# AMR3350.net
KiCad netlist of a schematic drawn in EAGLE
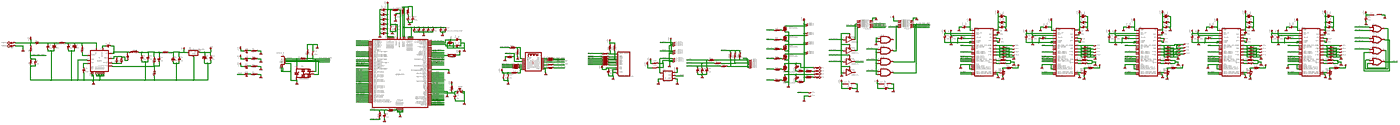
[diagram p0: schematic, sheet 1, overview]
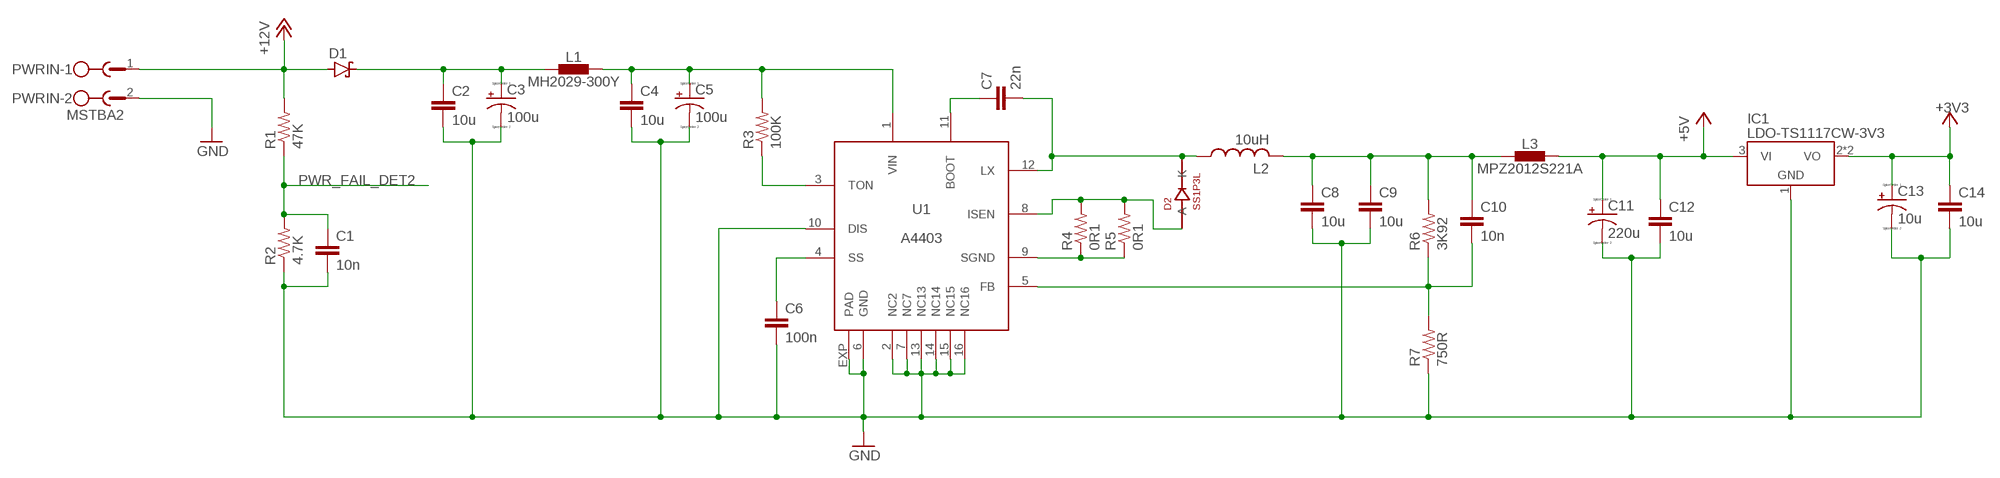
[diagram p1: schematic, sheet 1, part 1 of 8]
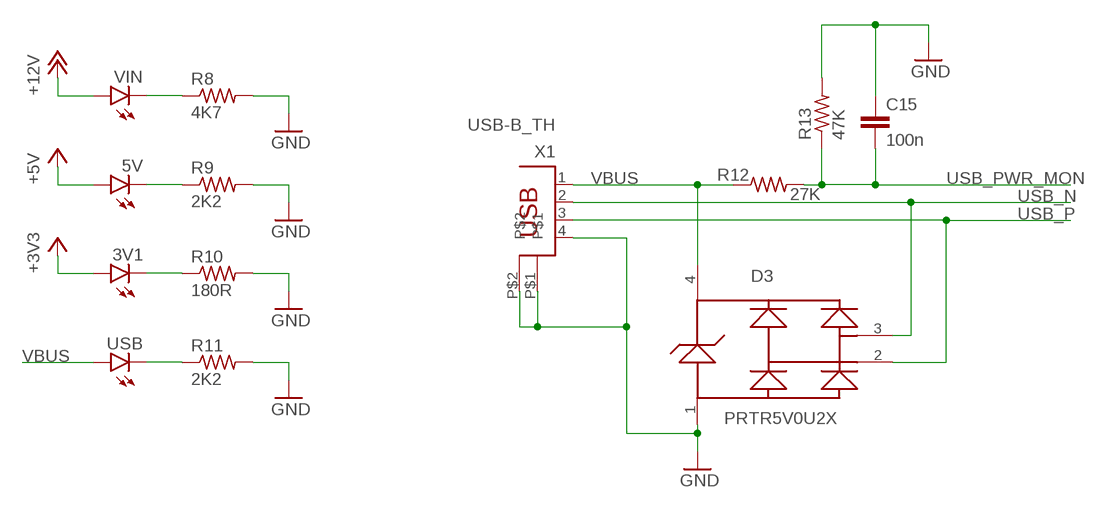
[diagram p2: schematic, sheet 1, part 2 of 8]
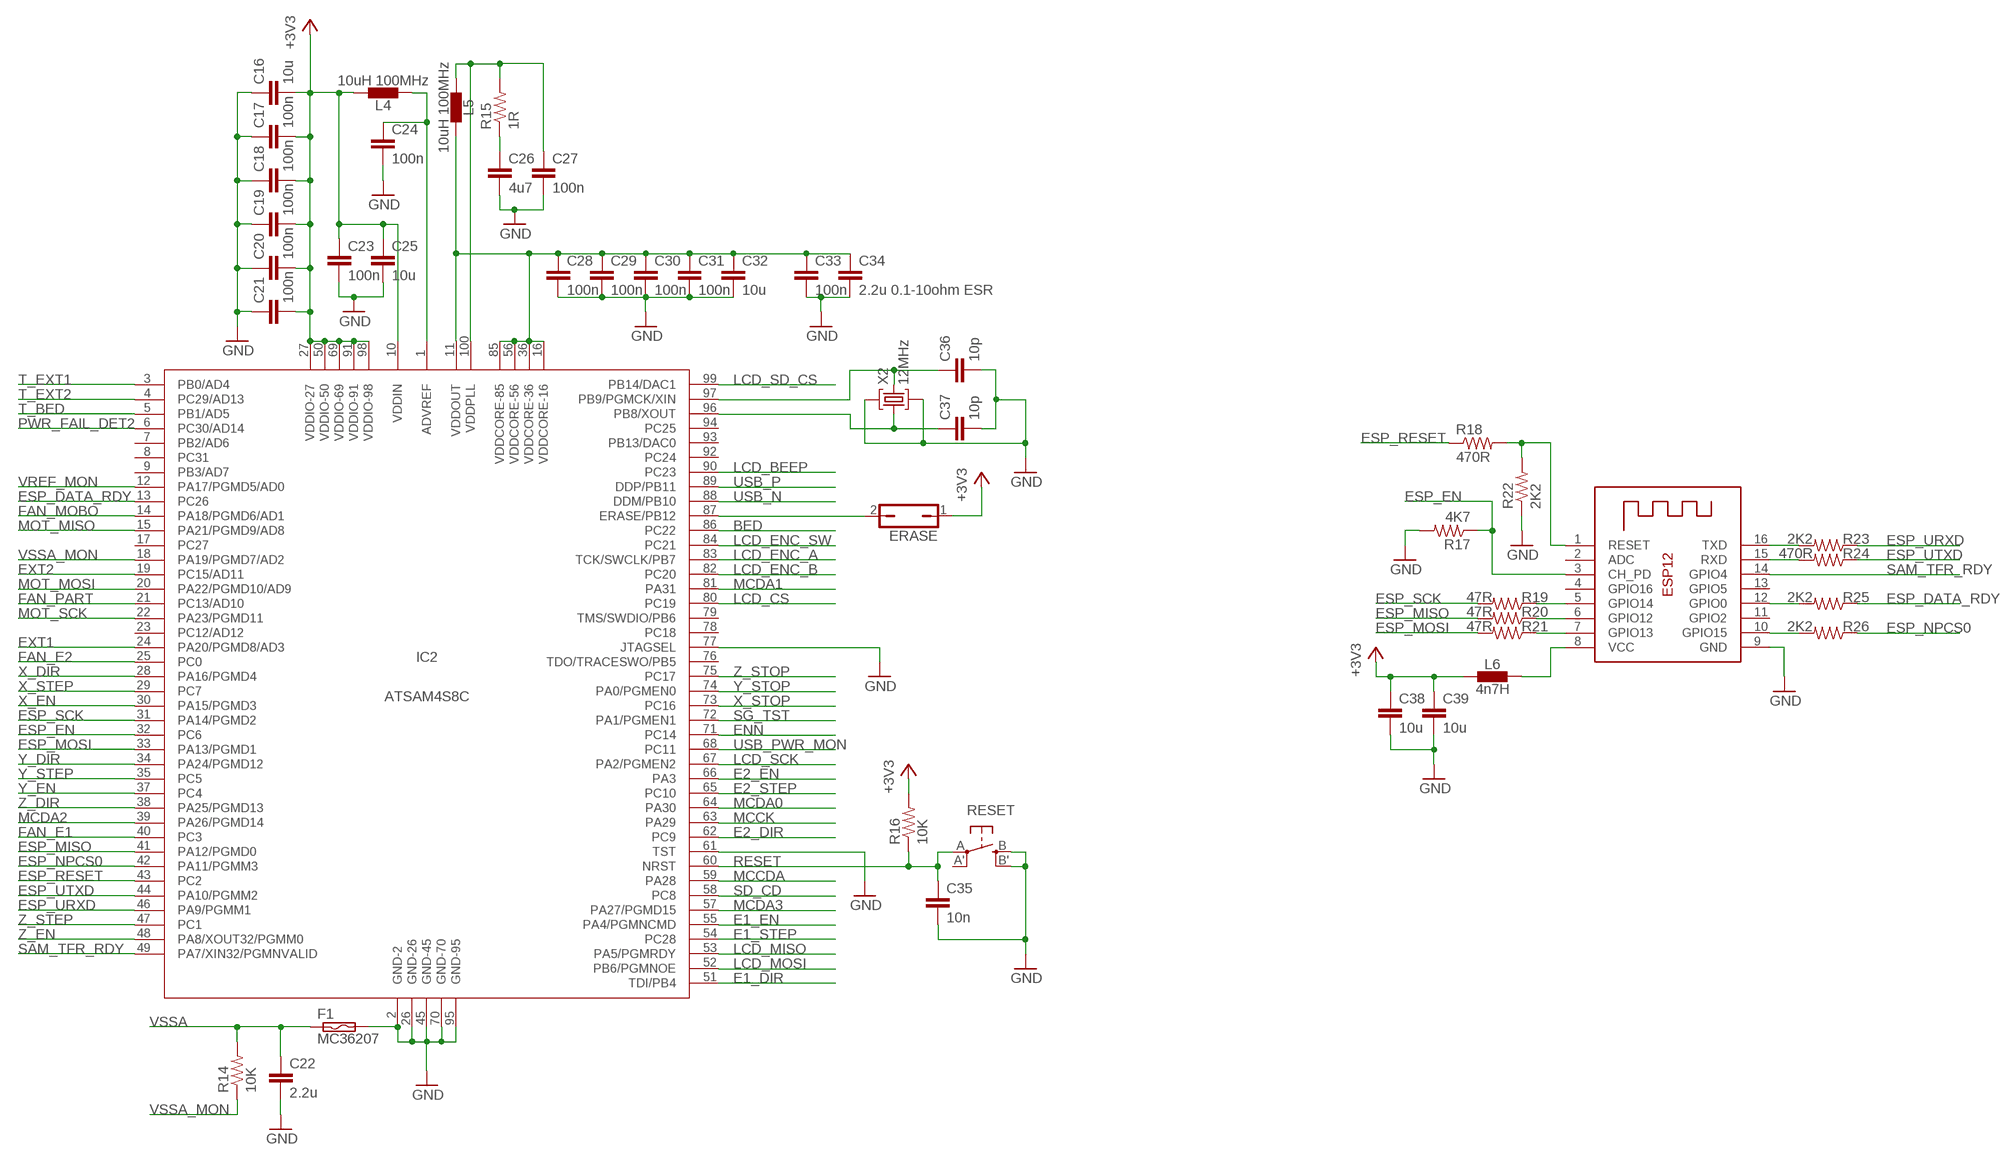
[diagram p3: schematic, sheet 1, part 3 of 8]
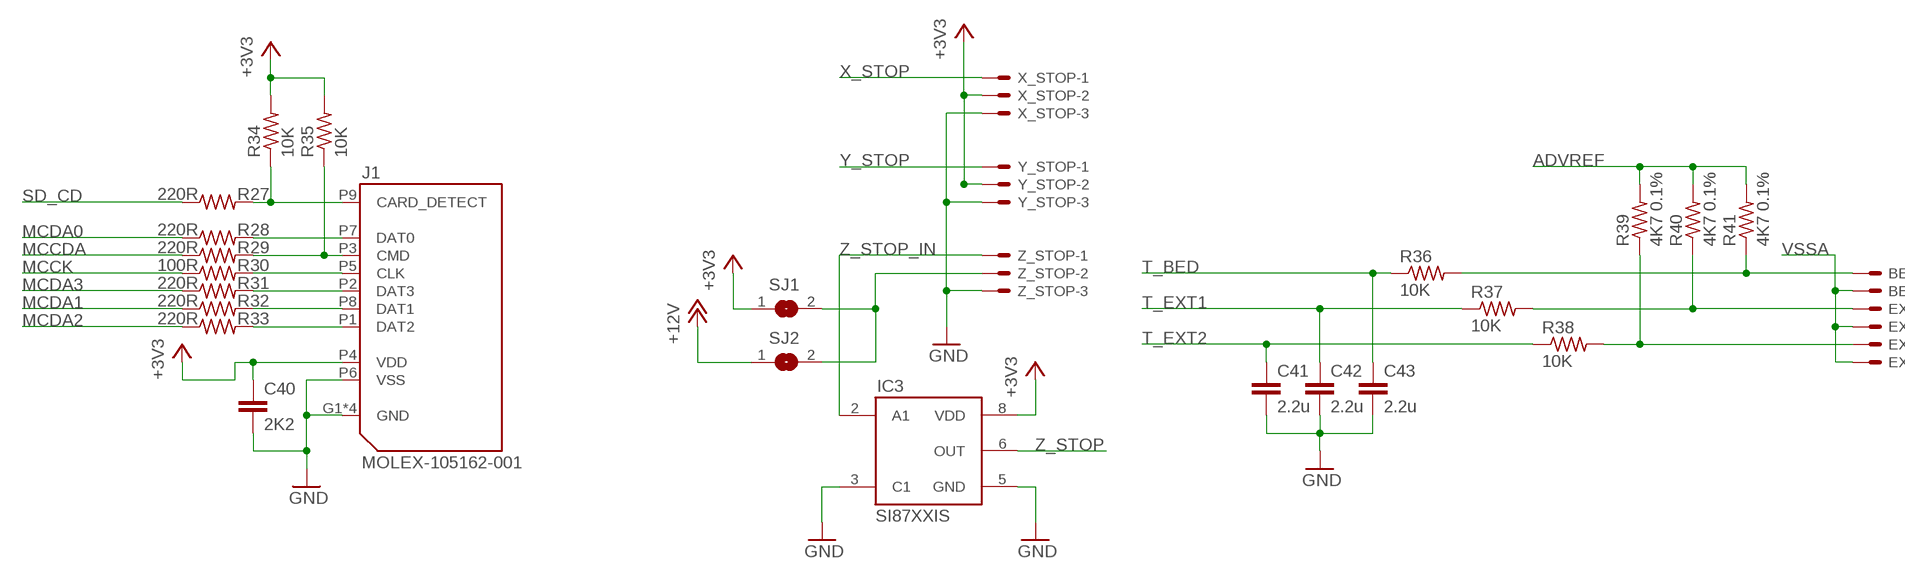
[diagram p4: schematic, sheet 1, part 4 of 8]
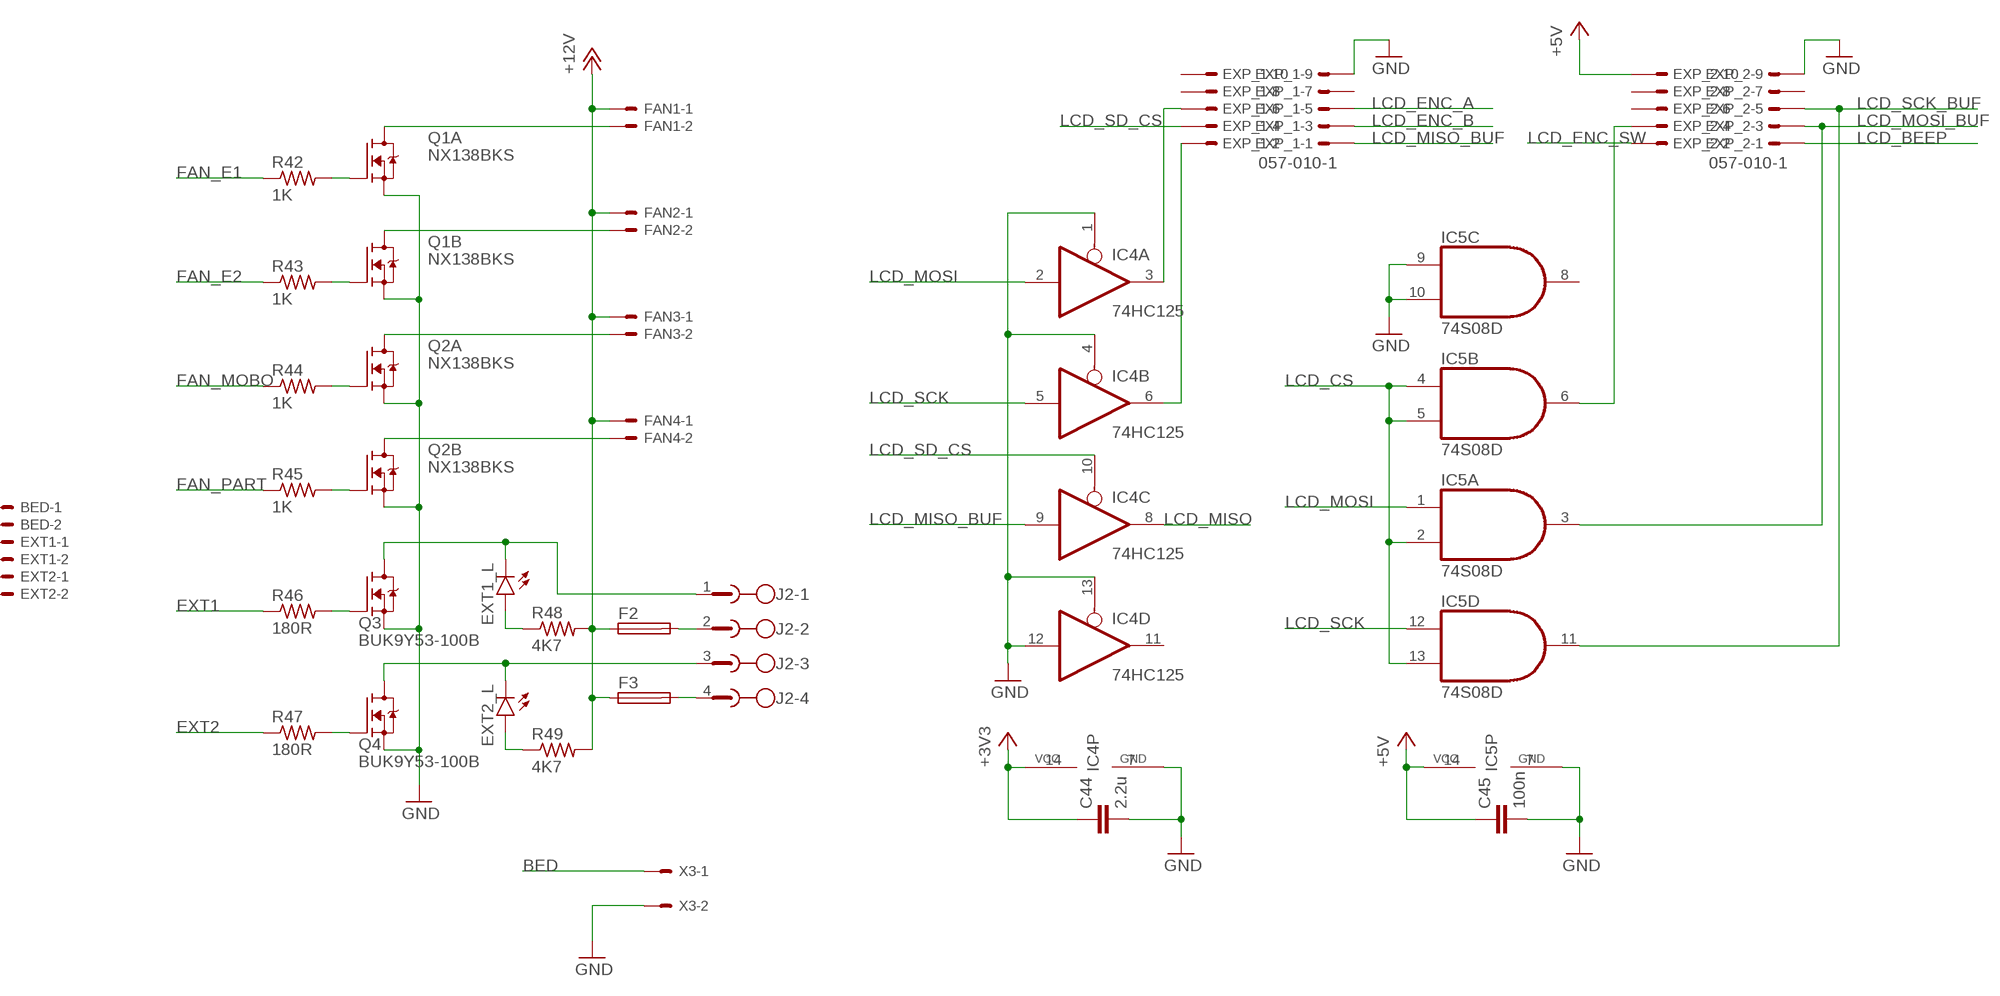
[diagram p5: schematic, sheet 1, part 5 of 8]
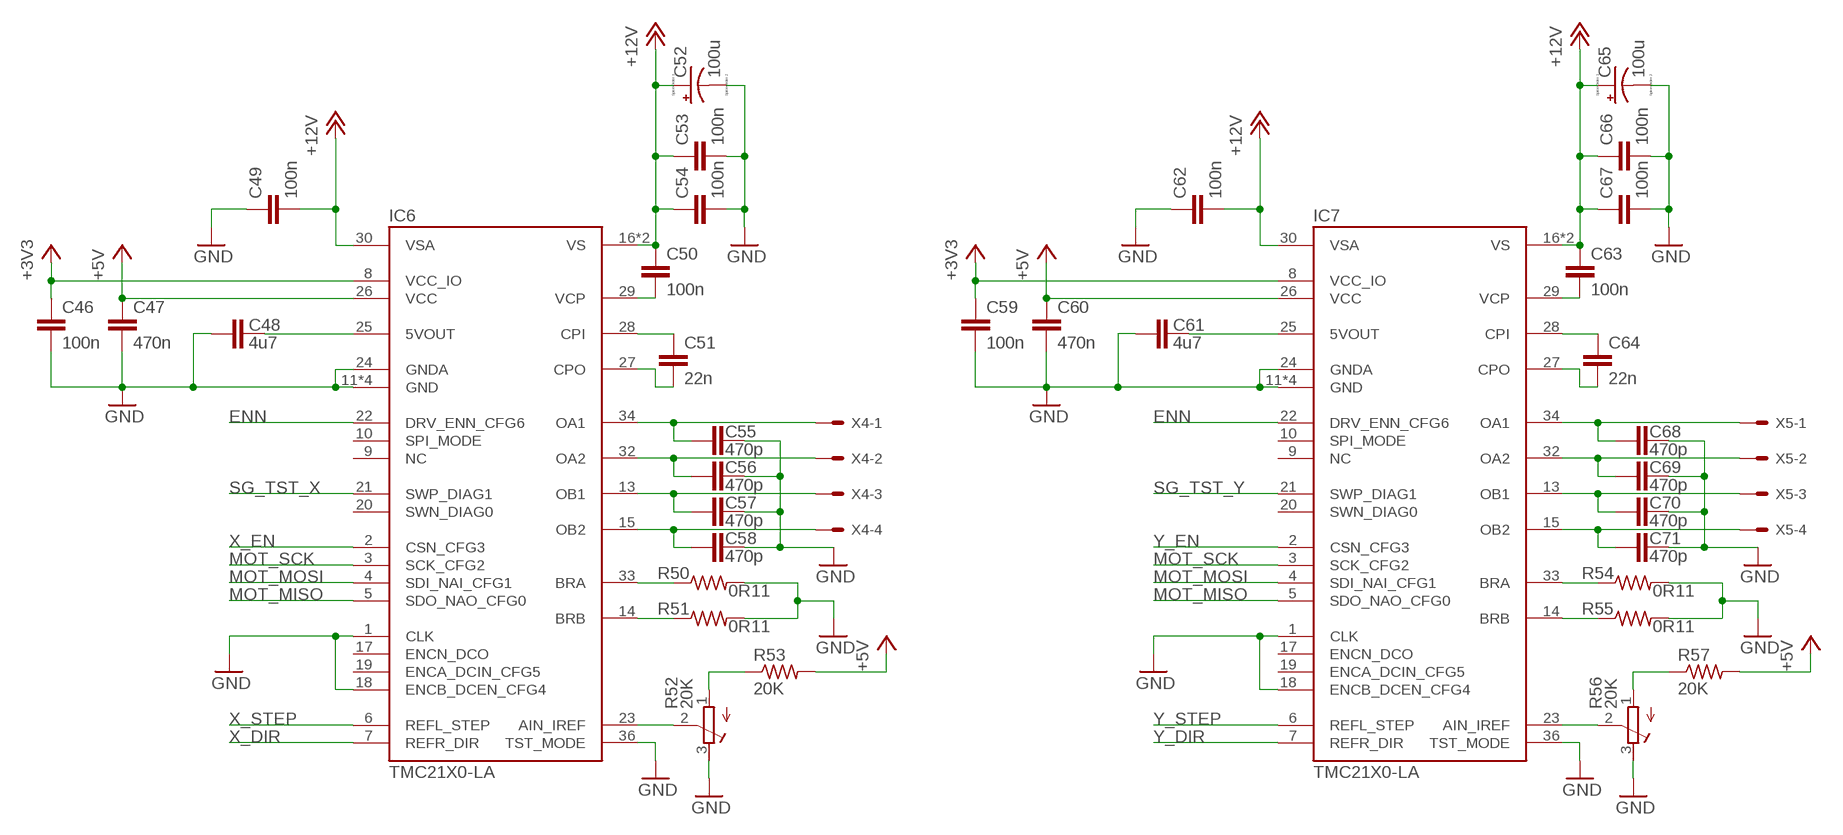
[diagram p6: schematic, sheet 1, part 6 of 8]
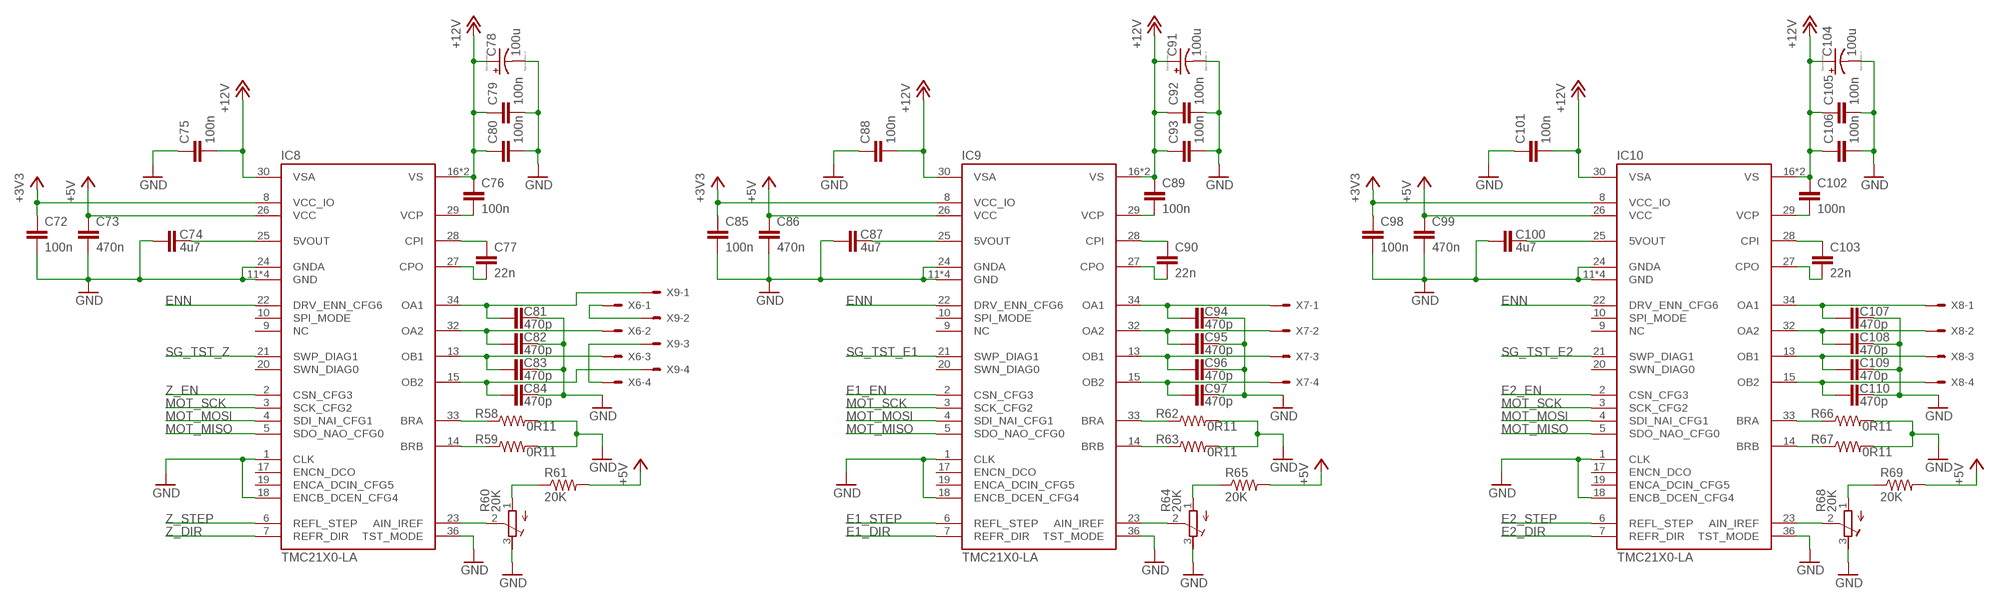
[diagram p7: schematic, sheet 1, part 7 of 8]
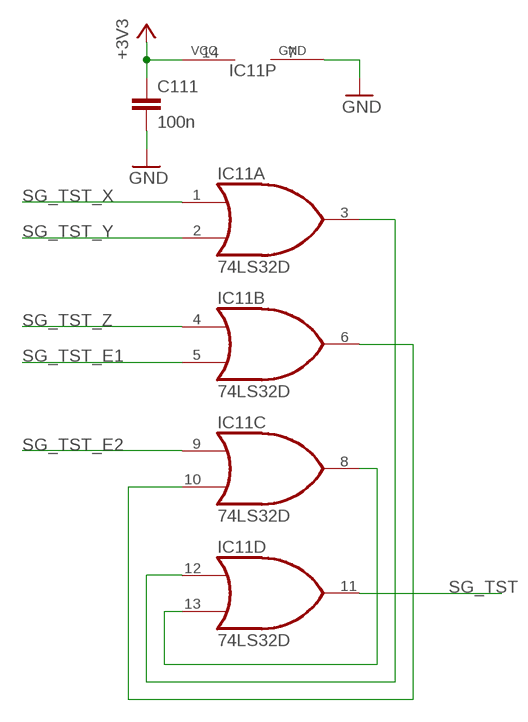
[diagram p8: schematic, sheet 1, part 8 of 8]

(export (version "E")
  (design (tool "Eeschema 10.0.6"))
  (components
    (comp (ref "3V1")
      (value "LEDCHIPLED_0805")
      (footprint "eagle-import:CHIPLED_0805")
      (libsource (lib "eagle-import") (part "LEDCHIPLED_0805"))
    )
    (comp (ref "5V")
      (value "LEDCHIPLED_0805")
      (footprint "eagle-import:CHIPLED_0805")
      (libsource (lib "eagle-import") (part "LEDCHIPLED_0805"))
    )
    (comp (ref "BED")
      (value "KK-254-2")
      (footprint "eagle-import:MOLEX-KK-254-2")
      (libsource (lib "eagle-import") (part "KK-254-2"))
    )
    (comp (ref "C1")
      (value "10n")
      (footprint "eagle-import:C0603")
      (libsource (lib "eagle-import") (part "resistor_348_C-EUC0603"))
    )
    (comp (ref "C2")
      (value "10u")
      (footprint "eagle-import:C0603")
      (libsource (lib "eagle-import") (part "resistor_348_C-EUC0603"))
    )
    (comp (ref "C3")
      (value "100u")
      (footprint "eagle-import:PANASONIC_D")
      (libsource (lib "eagle-import") (part "CPOL-USD"))
    )
    (comp (ref "C4")
      (value "10u")
      (footprint "eagle-import:C0603")
      (libsource (lib "eagle-import") (part "resistor_348_C-EUC0603"))
    )
    (comp (ref "C5")
      (value "100u")
      (footprint "eagle-import:PANASONIC_D")
      (libsource (lib "eagle-import") (part "CPOL-USD"))
    )
    (comp (ref "C6")
      (value "100n")
      (footprint "eagle-import:C0603")
      (libsource (lib "eagle-import") (part "resistor_348_C-EUC0603"))
    )
    (comp (ref "C7")
      (value "22n")
      (footprint "eagle-import:C0603")
      (libsource (lib "eagle-import") (part "resistor_348_C-EUC0603"))
    )
    (comp (ref "C8")
      (value "10u")
      (footprint "eagle-import:C0603")
      (libsource (lib "eagle-import") (part "resistor_348_C-EUC0603"))
    )
    (comp (ref "C9")
      (value "10u")
      (footprint "eagle-import:C0603")
      (libsource (lib "eagle-import") (part "resistor_348_C-EUC0603"))
    )
    (comp (ref "C10")
      (value "10n")
      (footprint "eagle-import:C0603")
      (libsource (lib "eagle-import") (part "resistor_348_C-EUC0603"))
    )
    (comp (ref "C11")
      (value "220u")
      (footprint "eagle-import:PANASONIC_D")
      (libsource (lib "eagle-import") (part "CPOL-USD"))
    )
    (comp (ref "C12")
      (value "10u")
      (footprint "eagle-import:C0603")
      (libsource (lib "eagle-import") (part "resistor_348_C-EUC0603"))
    )
    (comp (ref "C13")
      (value "10u")
      (footprint "eagle-import:PANASONIC_D")
      (libsource (lib "eagle-import") (part "CPOL-USD"))
    )
    (comp (ref "C14")
      (value "10u")
      (footprint "eagle-import:C0603")
      (libsource (lib "eagle-import") (part "resistor_348_C-EUC0603"))
    )
    (comp (ref "C15")
      (value "100n")
      (footprint "eagle-import:C0603")
      (libsource (lib "eagle-import") (part "resistor_348_C-EUC0603"))
    )
    (comp (ref "C16")
      (value "10u")
      (footprint "eagle-import:C0805")
      (libsource (lib "eagle-import") (part "resistor_348_C-EUC0805"))
    )
    (comp (ref "C17")
      (value "100n")
      (footprint "eagle-import:C0603")
      (libsource (lib "eagle-import") (part "resistor_348_C-EUC0603"))
    )
    (comp (ref "C18")
      (value "100n")
      (footprint "eagle-import:C0603")
      (libsource (lib "eagle-import") (part "resistor_348_C-EUC0603"))
    )
    (comp (ref "C19")
      (value "100n")
      (footprint "eagle-import:C0603")
      (libsource (lib "eagle-import") (part "resistor_348_C-EUC0603"))
    )
    (comp (ref "C20")
      (value "100n")
      (footprint "eagle-import:C0603")
      (libsource (lib "eagle-import") (part "resistor_348_C-EUC0603"))
    )
    (comp (ref "C21")
      (value "100n")
      (footprint "eagle-import:C0603")
      (libsource (lib "eagle-import") (part "resistor_348_C-EUC0603"))
    )
    (comp (ref "C22")
      (value "2.2u")
      (footprint "eagle-import:C0603")
      (libsource (lib "eagle-import") (part "resistor_348_C-EUC0603"))
    )
    (comp (ref "C23")
      (value "100n")
      (footprint "eagle-import:C0603")
      (libsource (lib "eagle-import") (part "resistor_348_C-EUC0603"))
    )
    (comp (ref "C24")
      (value "100n")
      (footprint "eagle-import:C0603")
      (libsource (lib "eagle-import") (part "resistor_348_C-EUC0603"))
    )
    (comp (ref "C25")
      (value "10u")
      (footprint "eagle-import:C0603")
      (libsource (lib "eagle-import") (part "resistor_348_C-EUC0603"))
    )
    (comp (ref "C26")
      (value "4u7")
      (footprint "eagle-import:C0603")
      (libsource (lib "eagle-import") (part "resistor_348_C-EUC0603"))
    )
    (comp (ref "C27")
      (value "100n")
      (footprint "eagle-import:C0603")
      (libsource (lib "eagle-import") (part "resistor_348_C-EUC0603"))
    )
    (comp (ref "C28")
      (value "100n")
      (footprint "eagle-import:C0603")
      (libsource (lib "eagle-import") (part "resistor_348_C-EUC0603"))
    )
    (comp (ref "C29")
      (value "100n")
      (footprint "eagle-import:C0603")
      (libsource (lib "eagle-import") (part "resistor_348_C-EUC0603"))
    )
    (comp (ref "C30")
      (value "100n")
      (footprint "eagle-import:C0603")
      (libsource (lib "eagle-import") (part "resistor_348_C-EUC0603"))
    )
    (comp (ref "C31")
      (value "100n")
      (footprint "eagle-import:C0603")
      (libsource (lib "eagle-import") (part "resistor_348_C-EUC0603"))
    )
    (comp (ref "C32")
      (value "10u")
      (footprint "eagle-import:C0805")
      (libsource (lib "eagle-import") (part "resistor_348_C-EUC0805"))
    )
    (comp (ref "C33")
      (value "100n")
      (footprint "eagle-import:C0603")
      (libsource (lib "eagle-import") (part "resistor_348_C-EUC0603"))
    )
    (comp (ref "C34")
      (value "2.2u 0.1-10ohm ESR")
      (footprint "eagle-import:C0603")
      (libsource (lib "eagle-import") (part "resistor_348_C-EUC0603"))
    )
    (comp (ref "C35")
      (value "10n")
      (footprint "eagle-import:C0603")
      (libsource (lib "eagle-import") (part "resistor_348_C-EUC0603"))
    )
    (comp (ref "C36")
      (value "10p")
      (footprint "eagle-import:C0603")
      (libsource (lib "eagle-import") (part "resistor_348_C-EUC0603"))
    )
    (comp (ref "C37")
      (value "10p")
      (footprint "eagle-import:C0603")
      (libsource (lib "eagle-import") (part "resistor_348_C-EUC0603"))
    )
    (comp (ref "C38")
      (value "10u")
      (footprint "eagle-import:C0603")
      (libsource (lib "eagle-import") (part "resistor_348_C-EUC0603"))
    )
    (comp (ref "C39")
      (value "10u")
      (footprint "eagle-import:C0603")
      (libsource (lib "eagle-import") (part "resistor_348_C-EUC0603"))
    )
    (comp (ref "C40")
      (value "2K2")
      (footprint "eagle-import:C0603")
      (libsource (lib "eagle-import") (part "resistor_348_C-EUC0603"))
    )
    (comp (ref "C41")
      (value "2.2u")
      (footprint "eagle-import:C0603")
      (libsource (lib "eagle-import") (part "resistor_348_C-EUC0603"))
    )
    (comp (ref "C42")
      (value "2.2u")
      (footprint "eagle-import:C0603")
      (libsource (lib "eagle-import") (part "resistor_348_C-EUC0603"))
    )
    (comp (ref "C43")
      (value "2.2u")
      (footprint "eagle-import:C0603")
      (libsource (lib "eagle-import") (part "resistor_348_C-EUC0603"))
    )
    (comp (ref "C44")
      (value "2.2u")
      (footprint "eagle-import:C0603")
      (libsource (lib "eagle-import") (part "resistor_348_C-EUC0603"))
    )
    (comp (ref "C45")
      (value "100n")
      (footprint "eagle-import:C0603")
      (libsource (lib "eagle-import") (part "resistor_348_C-EUC0603"))
    )
    (comp (ref "C46")
      (value "100n")
      (footprint "eagle-import:C0603")
      (libsource (lib "eagle-import") (part "resistor_348_C-EUC0603"))
    )
    (comp (ref "C47")
      (value "470n")
      (footprint "eagle-import:C0603")
      (libsource (lib "eagle-import") (part "resistor_348_C-EUC0603"))
    )
    (comp (ref "C48")
      (value "4u7")
      (footprint "eagle-import:C0603")
      (libsource (lib "eagle-import") (part "resistor_348_C-EUC0603"))
    )
    (comp (ref "C49")
      (value "100n")
      (footprint "eagle-import:C0603")
      (libsource (lib "eagle-import") (part "resistor_348_C-EUC0603"))
    )
    (comp (ref "C50")
      (value "100n")
      (footprint "eagle-import:C0603")
      (libsource (lib "eagle-import") (part "resistor_348_C-EUC0603"))
    )
    (comp (ref "C51")
      (value "22n")
      (footprint "eagle-import:C0603")
      (libsource (lib "eagle-import") (part "resistor_348_C-EUC0603"))
    )
    (comp (ref "C52")
      (value "100u")
      (footprint "eagle-import:PANASONIC_D")
      (libsource (lib "eagle-import") (part "CPOL-USD"))
    )
    (comp (ref "C53")
      (value "100n")
      (footprint "eagle-import:C0603")
      (libsource (lib "eagle-import") (part "resistor_348_C-EUC0603"))
    )
    (comp (ref "C54")
      (value "100n")
      (footprint "eagle-import:C0603")
      (libsource (lib "eagle-import") (part "resistor_348_C-EUC0603"))
    )
    (comp (ref "C55")
      (value "470p")
      (footprint "eagle-import:C0402")
      (libsource (lib "eagle-import") (part "resistor_348_C-EUC0402"))
    )
    (comp (ref "C56")
      (value "470p")
      (footprint "eagle-import:C0402")
      (libsource (lib "eagle-import") (part "resistor_348_C-EUC0402"))
    )
    (comp (ref "C57")
      (value "470p")
      (footprint "eagle-import:C0402")
      (libsource (lib "eagle-import") (part "resistor_348_C-EUC0402"))
    )
    (comp (ref "C58")
      (value "470p")
      (footprint "eagle-import:C0402")
      (libsource (lib "eagle-import") (part "resistor_348_C-EUC0402"))
    )
    (comp (ref "C59")
      (value "100n")
      (footprint "eagle-import:C0603")
      (libsource (lib "eagle-import") (part "resistor_348_C-EUC0603"))
    )
    (comp (ref "C60")
      (value "470n")
      (footprint "eagle-import:C0603")
      (libsource (lib "eagle-import") (part "resistor_348_C-EUC0603"))
    )
    (comp (ref "C61")
      (value "4u7")
      (footprint "eagle-import:C0603")
      (libsource (lib "eagle-import") (part "resistor_348_C-EUC0603"))
    )
    (comp (ref "C62")
      (value "100n")
      (footprint "eagle-import:C0603")
      (libsource (lib "eagle-import") (part "resistor_348_C-EUC0603"))
    )
    (comp (ref "C63")
      (value "100n")
      (footprint "eagle-import:C0603")
      (libsource (lib "eagle-import") (part "resistor_348_C-EUC0603"))
    )
    (comp (ref "C64")
      (value "22n")
      (footprint "eagle-import:C0603")
      (libsource (lib "eagle-import") (part "resistor_348_C-EUC0603"))
    )
    (comp (ref "C65")
      (value "100u")
      (footprint "eagle-import:PANASONIC_D")
      (libsource (lib "eagle-import") (part "CPOL-USD"))
    )
    (comp (ref "C66")
      (value "100n")
      (footprint "eagle-import:C0603")
      (libsource (lib "eagle-import") (part "resistor_348_C-EUC0603"))
    )
    (comp (ref "C67")
      (value "100n")
      (footprint "eagle-import:C0603")
      (libsource (lib "eagle-import") (part "resistor_348_C-EUC0603"))
    )
    (comp (ref "C68")
      (value "470p")
      (footprint "eagle-import:C0402")
      (libsource (lib "eagle-import") (part "resistor_348_C-EUC0402"))
    )
    (comp (ref "C69")
      (value "470p")
      (footprint "eagle-import:C0402")
      (libsource (lib "eagle-import") (part "resistor_348_C-EUC0402"))
    )
    (comp (ref "C70")
      (value "470p")
      (footprint "eagle-import:C0402")
      (libsource (lib "eagle-import") (part "resistor_348_C-EUC0402"))
    )
    (comp (ref "C71")
      (value "470p")
      (footprint "eagle-import:C0402")
      (libsource (lib "eagle-import") (part "resistor_348_C-EUC0402"))
    )
    (comp (ref "C72")
      (value "100n")
      (footprint "eagle-import:C0603")
      (libsource (lib "eagle-import") (part "resistor_348_C-EUC0603"))
    )
    (comp (ref "C73")
      (value "470n")
      (footprint "eagle-import:C0603")
      (libsource (lib "eagle-import") (part "resistor_348_C-EUC0603"))
    )
    (comp (ref "C74")
      (value "4u7")
      (footprint "eagle-import:C0603")
      (libsource (lib "eagle-import") (part "resistor_348_C-EUC0603"))
    )
    (comp (ref "C75")
      (value "100n")
      (footprint "eagle-import:C0603")
      (libsource (lib "eagle-import") (part "resistor_348_C-EUC0603"))
    )
    (comp (ref "C76")
      (value "100n")
      (footprint "eagle-import:C0603")
      (libsource (lib "eagle-import") (part "resistor_348_C-EUC0603"))
    )
    (comp (ref "C77")
      (value "22n")
      (footprint "eagle-import:C0603")
      (libsource (lib "eagle-import") (part "resistor_348_C-EUC0603"))
    )
    (comp (ref "C78")
      (value "100u")
      (footprint "eagle-import:PANASONIC_D")
      (libsource (lib "eagle-import") (part "CPOL-USD"))
    )
    (comp (ref "C79")
      (value "100n")
      (footprint "eagle-import:C0603")
      (libsource (lib "eagle-import") (part "resistor_348_C-EUC0603"))
    )
    (comp (ref "C80")
      (value "100n")
      (footprint "eagle-import:C0603")
      (libsource (lib "eagle-import") (part "resistor_348_C-EUC0603"))
    )
    (comp (ref "C81")
      (value "470p")
      (footprint "eagle-import:C0402")
      (libsource (lib "eagle-import") (part "resistor_348_C-EUC0402"))
    )
    (comp (ref "C82")
      (value "470p")
      (footprint "eagle-import:C0402")
      (libsource (lib "eagle-import") (part "resistor_348_C-EUC0402"))
    )
    (comp (ref "C83")
      (value "470p")
      (footprint "eagle-import:C0402")
      (libsource (lib "eagle-import") (part "resistor_348_C-EUC0402"))
    )
    (comp (ref "C84")
      (value "470p")
      (footprint "eagle-import:C0402")
      (libsource (lib "eagle-import") (part "resistor_348_C-EUC0402"))
    )
    (comp (ref "C85")
      (value "100n")
      (footprint "eagle-import:C0603")
      (libsource (lib "eagle-import") (part "resistor_348_C-EUC0603"))
    )
    (comp (ref "C86")
      (value "470n")
      (footprint "eagle-import:C0603")
      (libsource (lib "eagle-import") (part "resistor_348_C-EUC0603"))
    )
    (comp (ref "C87")
      (value "4u7")
      (footprint "eagle-import:C0603")
      (libsource (lib "eagle-import") (part "resistor_348_C-EUC0603"))
    )
    (comp (ref "C88")
      (value "100n")
      (footprint "eagle-import:C0603")
      (libsource (lib "eagle-import") (part "resistor_348_C-EUC0603"))
    )
    (comp (ref "C89")
      (value "100n")
      (footprint "eagle-import:C0603")
      (libsource (lib "eagle-import") (part "resistor_348_C-EUC0603"))
    )
    (comp (ref "C90")
      (value "22n")
      (footprint "eagle-import:C0603")
      (libsource (lib "eagle-import") (part "resistor_348_C-EUC0603"))
    )
    (comp (ref "C91")
      (value "100u")
      (footprint "eagle-import:PANASONIC_D")
      (libsource (lib "eagle-import") (part "CPOL-USD"))
    )
    (comp (ref "C92")
      (value "100n")
      (footprint "eagle-import:C0603")
      (libsource (lib "eagle-import") (part "resistor_348_C-EUC0603"))
    )
    (comp (ref "C93")
      (value "100n")
      (footprint "eagle-import:C0603")
      (libsource (lib "eagle-import") (part "resistor_348_C-EUC0603"))
    )
    (comp (ref "C94")
      (value "470p")
      (footprint "eagle-import:C0402")
      (libsource (lib "eagle-import") (part "resistor_348_C-EUC0402"))
    )
    (comp (ref "C95")
      (value "470p")
      (footprint "eagle-import:C0402")
      (libsource (lib "eagle-import") (part "resistor_348_C-EUC0402"))
    )
    (comp (ref "C96")
      (value "470p")
      (footprint "eagle-import:C0402")
      (libsource (lib "eagle-import") (part "resistor_348_C-EUC0402"))
    )
    (comp (ref "C97")
      (value "470p")
      (footprint "eagle-import:C0402")
      (libsource (lib "eagle-import") (part "resistor_348_C-EUC0402"))
    )
    (comp (ref "C98")
      (value "100n")
      (footprint "eagle-import:C0603")
      (libsource (lib "eagle-import") (part "resistor_348_C-EUC0603"))
    )
    (comp (ref "C99")
      (value "470n")
      (footprint "eagle-import:C0603")
      (libsource (lib "eagle-import") (part "resistor_348_C-EUC0603"))
    )
    (comp (ref "C100")
      (value "4u7")
      (footprint "eagle-import:C0603")
      (libsource (lib "eagle-import") (part "resistor_348_C-EUC0603"))
    )
    (comp (ref "C101")
      (value "100n")
      (footprint "eagle-import:C0603")
      (libsource (lib "eagle-import") (part "resistor_348_C-EUC0603"))
    )
    (comp (ref "C102")
      (value "100n")
      (footprint "eagle-import:C0603")
      (libsource (lib "eagle-import") (part "resistor_348_C-EUC0603"))
    )
    (comp (ref "C103")
      (value "22n")
      (footprint "eagle-import:C0603")
      (libsource (lib "eagle-import") (part "resistor_348_C-EUC0603"))
    )
    (comp (ref "C104")
      (value "100u")
      (footprint "eagle-import:PANASONIC_D")
      (libsource (lib "eagle-import") (part "CPOL-USD"))
    )
    (comp (ref "C105")
      (value "100n")
      (footprint "eagle-import:C0603")
      (libsource (lib "eagle-import") (part "resistor_348_C-EUC0603"))
    )
    (comp (ref "C106")
      (value "100n")
      (footprint "eagle-import:C0603")
      (libsource (lib "eagle-import") (part "resistor_348_C-EUC0603"))
    )
    (comp (ref "C107")
      (value "470p")
      (footprint "eagle-import:C0402")
      (libsource (lib "eagle-import") (part "resistor_348_C-EUC0402"))
    )
    (comp (ref "C108")
      (value "470p")
      (footprint "eagle-import:C0402")
      (libsource (lib "eagle-import") (part "resistor_348_C-EUC0402"))
    )
    (comp (ref "C109")
      (value "470p")
      (footprint "eagle-import:C0402")
      (libsource (lib "eagle-import") (part "resistor_348_C-EUC0402"))
    )
    (comp (ref "C110")
      (value "470p")
      (footprint "eagle-import:C0402")
      (libsource (lib "eagle-import") (part "resistor_348_C-EUC0402"))
    )
    (comp (ref "C111")
      (value "100n")
      (footprint "eagle-import:C0603")
      (libsource (lib "eagle-import") (part "C-EUC0603"))
    )
    (comp (ref "D1")
      (value "SCHOTTKY-DIODESMD")
      (footprint "eagle-import:SMB")
      (libsource (lib "eagle-import") (part "SCHOTTKY-DIODESMD"))
    )
    (comp (ref "D2")
      (value "SS1P3L")
      (footprint "eagle-import:DO220AAL")
      (fields (field (name "PART_NUMBER") "SS1P3L-M3/84A"))
      (libsource (lib "eagle-import") (part "0025_SS1P3L-M3/84A"))
    )
    (comp (ref "D3")
      (value "PRTR5V0U2XB")
      (footprint "eagle-import:SOT143B")
      (libsource (lib "eagle-import") (part "PRTR5V0U2XB"))
    )
    (comp (ref "ERASE")
      (value "JP1Q")
      (footprint "eagle-import:JP1")
      (libsource (lib "eagle-import") (part "JP1Q"))
    )
    (comp (ref "ESP1")
      (value "ESP-12")
      (footprint "eagle-import:ESP-12")
      (libsource (lib "eagle-import") (part "ESP-12"))
    )
    (comp (ref "EXP_1")
      (value "057-010-1")
      (footprint "eagle-import:057-010-1")
      (libsource (lib "eagle-import") (part "057-010-1"))
    )
    (comp (ref "EXP_2")
      (value "057-010-1")
      (footprint "eagle-import:057-010-1")
      (libsource (lib "eagle-import") (part "057-010-1"))
    )
    (comp (ref "EXT1")
      (value "KK-254-2")
      (footprint "eagle-import:MOLEX-KK-254-2")
      (libsource (lib "eagle-import") (part "KK-254-2"))
    )
    (comp (ref "EXT1_L")
      (value "LEDCHIPLED_0805")
      (footprint "eagle-import:CHIPLED_0805")
      (libsource (lib "eagle-import") (part "LEDCHIPLED_0805"))
    )
    (comp (ref "EXT2")
      (value "KK-254-2")
      (footprint "eagle-import:MOLEX-KK-254-2")
      (libsource (lib "eagle-import") (part "KK-254-2"))
    )
    (comp (ref "EXT2_L")
      (value "LEDCHIPLED_0805")
      (footprint "eagle-import:CHIPLED_0805")
      (libsource (lib "eagle-import") (part "LEDCHIPLED_0805"))
    )
    (comp (ref "F1")
      (value "MC36207")
      (footprint "eagle-import:MC36207")
      (libsource (lib "eagle-import") (part "MC36207"))
    )
    (comp (ref "F2")
      (value "19560")
      (footprint "eagle-import:19560")
      (fields (field (name "MPN") "56000001009"))
      (libsource (lib "eagle-import") (part "19560"))
    )
    (comp (ref "F3")
      (value "19560")
      (footprint "eagle-import:19560")
      (fields (field (name "MPN") "56000001009"))
      (libsource (lib "eagle-import") (part "19560"))
    )
    (comp (ref "FAN1")
      (value "KK-254-2")
      (footprint "eagle-import:MOLEX-KK-254-2")
      (libsource (lib "eagle-import") (part "KK-254-2"))
    )
    (comp (ref "FAN2")
      (value "KK-254-2")
      (footprint "eagle-import:MOLEX-KK-254-2")
      (libsource (lib "eagle-import") (part "KK-254-2"))
    )
    (comp (ref "FAN3")
      (value "KK-254-2")
      (footprint "eagle-import:MOLEX-KK-254-2")
      (libsource (lib "eagle-import") (part "KK-254-2"))
    )
    (comp (ref "FAN4")
      (value "KK-254-2")
      (footprint "eagle-import:MOLEX-KK-254-2")
      (libsource (lib "eagle-import") (part "KK-254-2"))
    )
    (comp (ref "IC1")
      (value "LDO-TS1117CW-3V3")
      (footprint "eagle-import:SOT223")
      (libsource (lib "eagle-import") (part "LDO-TS1117CW-3V3"))
    )
    (comp (ref "IC2")
      (value "ATSAM4S8C")
      (footprint "eagle-import:LQFP100")
      (libsource (lib "eagle-import") (part "ATSAM4S8C"))
    )
    (comp (ref "IC3")
      (value "SI87XXIS")
      (footprint "eagle-import:SOIC08-FAIRCHILD")
      (libsource (lib "eagle-import") (part "SI87XXIS"))
    )
    (comp (ref "IC4")
      (value "74HC125")
      (footprint "eagle-import:SO14")
      (libsource (lib "eagle-import") (part "74HC125"))
    )
    (comp (ref "IC5")
      (value "74S08D")
      (footprint "eagle-import:SO14")
      (libsource (lib "eagle-import") (part "7408DS"))
    )
    (comp (ref "IC6")
      (value "TMC21X0-LA")
      (footprint "eagle-import:QFN36-PAD")
      (libsource (lib "eagle-import") (part "TMC21X0-LA"))
    )
    (comp (ref "IC7")
      (value "TMC21X0-LA")
      (footprint "eagle-import:QFN36-PAD")
      (libsource (lib "eagle-import") (part "TMC21X0-LA"))
    )
    (comp (ref "IC8")
      (value "TMC21X0-LA")
      (footprint "eagle-import:QFN36-PAD")
      (libsource (lib "eagle-import") (part "TMC21X0-LA"))
    )
    (comp (ref "IC9")
      (value "TMC21X0-LA")
      (footprint "eagle-import:QFN36-PAD")
      (libsource (lib "eagle-import") (part "TMC21X0-LA"))
    )
    (comp (ref "IC10")
      (value "TMC21X0-LA")
      (footprint "eagle-import:QFN36-PAD")
      (libsource (lib "eagle-import") (part "TMC21X0-LA"))
    )
    (comp (ref "IC11")
      (value "74LS32D")
      (footprint "eagle-import:SO14")
      (libsource (lib "eagle-import") (part "7432DLS"))
    )
    (comp (ref "J1")
      (value "MOLEX-105162-001")
      (footprint "eagle-import:MOLEX-105162")
      (libsource (lib "eagle-import") (part "MOLEX-105162-001"))
    )
    (comp (ref "J2")
      (value "MSTBV4")
      (footprint "eagle-import:MSTBV4")
      (fields (field (name "MPN") "MSTBV 2,5/4-GF-5.08"))
      (libsource (lib "eagle-import") (part "MSTBV4"))
    )
    (comp (ref "L1")
      (value "MH2029-300Y")
      (footprint "eagle-import:C0805")
      (libsource (lib "eagle-import") (part "INDUCTOR-0805"))
    )
    (comp (ref "L2")
      (value "10uH")
      (footprint "eagle-import:SRR0604")
      (libsource (lib "eagle-import") (part "L-USSRR0604"))
    )
    (comp (ref "L3")
      (value "MPZ2012S221A")
      (footprint "eagle-import:C0805")
      (libsource (lib "eagle-import") (part "INDUCTOR-0805"))
    )
    (comp (ref "L4")
      (value "10uH 100MHz")
      (footprint "eagle-import:C0603")
      (libsource (lib "eagle-import") (part "Zero_V1.0_INDUCTOR-0603"))
    )
    (comp (ref "L5")
      (value "10uH 100MHz")
      (footprint "eagle-import:C0603")
      (libsource (lib "eagle-import") (part "Zero_V1.0_INDUCTOR-0603"))
    )
    (comp (ref "L6")
      (value "4n7H")
      (footprint "eagle-import:C0603")
      (libsource (lib "eagle-import") (part "Zero_V1.0_INDUCTOR-0603"))
    )
    (comp (ref "PWRIN")
      (value "MSTBA2")
      (footprint "eagle-import:MSTBA2")
      (fields (field (name "MF") "FARNELL") (field (name "MPN") "1757242"))
      (libsource (lib "eagle-import") (part "MSTBA2"))
    )
    (comp (ref "Q1")
      (value "NX138BKS")
      (footprint "eagle-import:SOT363_PHILIPS")
      (libsource (lib "eagle-import") (part "NX138BKS"))
    )
    (comp (ref "Q2")
      (value "NX138BKS")
      (footprint "eagle-import:SOT363_PHILIPS")
      (libsource (lib "eagle-import") (part "NX138BKS"))
    )
    (comp (ref "Q3")
      (value "BUK9Y53-100B")
      (footprint "eagle-import:SOT-669")
      (libsource (lib "eagle-import") (part "BUK9Y53-100B"))
    )
    (comp (ref "Q4")
      (value "BUK9Y53-100B")
      (footprint "eagle-import:SOT-669")
      (libsource (lib "eagle-import") (part "BUK9Y53-100B"))
    )
    (comp (ref "R1")
      (value "47K")
      (footprint "eagle-import:R0603")
      (libsource (lib "eagle-import") (part "R-US_R0603"))
    )
    (comp (ref "R2")
      (value "4.7K")
      (footprint "eagle-import:R0603")
      (libsource (lib "eagle-import") (part "R-US_R0603"))
    )
    (comp (ref "R3")
      (value "100K")
      (footprint "eagle-import:R0603")
      (libsource (lib "eagle-import") (part "R-US_R0603"))
    )
    (comp (ref "R4")
      (value "0R1")
      (footprint "eagle-import:R0603")
      (libsource (lib "eagle-import") (part "R-US_R0603"))
    )
    (comp (ref "R5")
      (value "0R1")
      (footprint "eagle-import:R0603")
      (libsource (lib "eagle-import") (part "R-US_R0603"))
    )
    (comp (ref "R6")
      (value "3K92")
      (footprint "eagle-import:R0603")
      (libsource (lib "eagle-import") (part "R-US_R0603"))
    )
    (comp (ref "R7")
      (value "750R")
      (footprint "eagle-import:R0603")
      (libsource (lib "eagle-import") (part "R-US_R0603"))
    )
    (comp (ref "R8")
      (value "4K7")
      (footprint "eagle-import:R0603")
      (libsource (lib "eagle-import") (part "R-US_R0603"))
    )
    (comp (ref "R9")
      (value "2K2")
      (footprint "eagle-import:R0603")
      (libsource (lib "eagle-import") (part "R-US_R0603"))
    )
    (comp (ref "R10")
      (value "180R")
      (footprint "eagle-import:R0603")
      (libsource (lib "eagle-import") (part "R-US_R0603"))
    )
    (comp (ref "R11")
      (value "2K2")
      (footprint "eagle-import:R0603")
      (libsource (lib "eagle-import") (part "R-US_R0603"))
    )
    (comp (ref "R12")
      (value "27K")
      (footprint "eagle-import:R0603")
      (libsource (lib "eagle-import") (part "R-US_R0603"))
    )
    (comp (ref "R13")
      (value "47K")
      (footprint "eagle-import:R0603")
      (libsource (lib "eagle-import") (part "R-US_R0603"))
    )
    (comp (ref "R14")
      (value "10K")
      (footprint "eagle-import:R0603")
      (libsource (lib "eagle-import") (part "R-US_R0603"))
    )
    (comp (ref "R15")
      (value "1R")
      (footprint "eagle-import:R0603")
      (libsource (lib "eagle-import") (part "R-US_R0603"))
    )
    (comp (ref "R16")
      (value "10K")
      (footprint "eagle-import:R0603")
      (libsource (lib "eagle-import") (part "R-US_R0603"))
    )
    (comp (ref "R17")
      (value "4K7")
      (footprint "eagle-import:R0603")
      (libsource (lib "eagle-import") (part "R-US_R0603"))
    )
    (comp (ref "R18")
      (value "470R")
      (footprint "eagle-import:R0603")
      (libsource (lib "eagle-import") (part "R-US_R0603"))
    )
    (comp (ref "R19")
      (value "47R")
      (footprint "eagle-import:R0603")
      (libsource (lib "eagle-import") (part "R-US_R0603"))
    )
    (comp (ref "R20")
      (value "47R")
      (footprint "eagle-import:R0603")
      (libsource (lib "eagle-import") (part "R-US_R0603"))
    )
    (comp (ref "R21")
      (value "47R")
      (footprint "eagle-import:R0603")
      (libsource (lib "eagle-import") (part "R-US_R0603"))
    )
    (comp (ref "R22")
      (value "2K2")
      (footprint "eagle-import:R0603")
      (libsource (lib "eagle-import") (part "R-US_R0603"))
    )
    (comp (ref "R23")
      (value "2K2")
      (footprint "eagle-import:R0603")
      (libsource (lib "eagle-import") (part "R-US_R0603"))
    )
    (comp (ref "R24")
      (value "470R")
      (footprint "eagle-import:R0603")
      (libsource (lib "eagle-import") (part "R-US_R0603"))
    )
    (comp (ref "R25")
      (value "2K2")
      (footprint "eagle-import:R0603")
      (libsource (lib "eagle-import") (part "R-US_R0603"))
    )
    (comp (ref "R26")
      (value "2K2")
      (footprint "eagle-import:R0603")
      (libsource (lib "eagle-import") (part "R-US_R0603"))
    )
    (comp (ref "R27")
      (value "220R")
      (footprint "eagle-import:R0603")
      (libsource (lib "eagle-import") (part "R-US_R0603"))
    )
    (comp (ref "R28")
      (value "220R")
      (footprint "eagle-import:R0603")
      (libsource (lib "eagle-import") (part "R-US_R0603"))
    )
    (comp (ref "R29")
      (value "220R")
      (footprint "eagle-import:R0603")
      (libsource (lib "eagle-import") (part "R-US_R0603"))
    )
    (comp (ref "R30")
      (value "100R")
      (footprint "eagle-import:R0603")
      (libsource (lib "eagle-import") (part "R-US_R0603"))
    )
    (comp (ref "R31")
      (value "220R")
      (footprint "eagle-import:R0603")
      (libsource (lib "eagle-import") (part "R-US_R0603"))
    )
    (comp (ref "R32")
      (value "220R")
      (footprint "eagle-import:R0603")
      (libsource (lib "eagle-import") (part "R-US_R0603"))
    )
    (comp (ref "R33")
      (value "220R")
      (footprint "eagle-import:R0603")
      (libsource (lib "eagle-import") (part "R-US_R0603"))
    )
    (comp (ref "R34")
      (value "10K")
      (footprint "eagle-import:R0603")
      (libsource (lib "eagle-import") (part "R-US_R0603"))
    )
    (comp (ref "R35")
      (value "10K")
      (footprint "eagle-import:R0603")
      (libsource (lib "eagle-import") (part "R-US_R0603"))
    )
    (comp (ref "R36")
      (value "10K")
      (footprint "eagle-import:R0603")
      (libsource (lib "eagle-import") (part "R-US_R0603"))
    )
    (comp (ref "R37")
      (value "10K")
      (footprint "eagle-import:R0603")
      (libsource (lib "eagle-import") (part "R-US_R0603"))
    )
    (comp (ref "R38")
      (value "10K")
      (footprint "eagle-import:R0603")
      (libsource (lib "eagle-import") (part "R-US_R0603"))
    )
    (comp (ref "R39")
      (value "4K7 0.1%")
      (footprint "eagle-import:R0603")
      (libsource (lib "eagle-import") (part "R-US_R0603"))
    )
    (comp (ref "R40")
      (value "4K7 0.1%")
      (footprint "eagle-import:R0603")
      (libsource (lib "eagle-import") (part "R-US_R0603"))
    )
    (comp (ref "R41")
      (value "4K7 0.1%")
      (footprint "eagle-import:R0603")
      (libsource (lib "eagle-import") (part "R-US_R0603"))
    )
    (comp (ref "R42")
      (value "1K")
      (footprint "eagle-import:R0603")
      (libsource (lib "eagle-import") (part "R-US_R0603"))
    )
    (comp (ref "R43")
      (value "1K")
      (footprint "eagle-import:R0603")
      (libsource (lib "eagle-import") (part "R-US_R0603"))
    )
    (comp (ref "R44")
      (value "1K")
      (footprint "eagle-import:R0603")
      (libsource (lib "eagle-import") (part "R-US_R0603"))
    )
    (comp (ref "R45")
      (value "1K")
      (footprint "eagle-import:R0603")
      (libsource (lib "eagle-import") (part "R-US_R0603"))
    )
    (comp (ref "R46")
      (value "180R")
      (footprint "eagle-import:R0603")
      (libsource (lib "eagle-import") (part "R-US_R0603"))
    )
    (comp (ref "R47")
      (value "180R")
      (footprint "eagle-import:R0603")
      (libsource (lib "eagle-import") (part "R-US_R0603"))
    )
    (comp (ref "R48")
      (value "4K7")
      (footprint "eagle-import:R0603")
      (libsource (lib "eagle-import") (part "R-US_R0603"))
    )
    (comp (ref "R49")
      (value "4K7")
      (footprint "eagle-import:R0603")
      (libsource (lib "eagle-import") (part "R-US_R0603"))
    )
    (comp (ref "R50")
      (value "0R11")
      (footprint "eagle-import:R1206")
      (libsource (lib "eagle-import") (part "R-US_R1206"))
    )
    (comp (ref "R51")
      (value "0R11")
      (footprint "eagle-import:R1206")
      (libsource (lib "eagle-import") (part "R-US_R1206"))
    )
    (comp (ref "R52")
      (value "20K")
      (footprint "eagle-import:RTRIM3103")
      (libsource (lib "eagle-import") (part "R-TRIMM3103"))
    )
    (comp (ref "R53")
      (value "20K")
      (footprint "eagle-import:R0603")
      (libsource (lib "eagle-import") (part "R-US_R0603"))
    )
    (comp (ref "R54")
      (value "0R11")
      (footprint "eagle-import:R1206")
      (libsource (lib "eagle-import") (part "R-US_R1206"))
    )
    (comp (ref "R55")
      (value "0R11")
      (footprint "eagle-import:R1206")
      (libsource (lib "eagle-import") (part "R-US_R1206"))
    )
    (comp (ref "R56")
      (value "20K")
      (footprint "eagle-import:RTRIM3103")
      (libsource (lib "eagle-import") (part "R-TRIMM3103"))
    )
    (comp (ref "R57")
      (value "20K")
      (footprint "eagle-import:R0603")
      (libsource (lib "eagle-import") (part "R-US_R0603"))
    )
    (comp (ref "R58")
      (value "0R11")
      (footprint "eagle-import:R1206")
      (libsource (lib "eagle-import") (part "R-US_R1206"))
    )
    (comp (ref "R59")
      (value "0R11")
      (footprint "eagle-import:R1206")
      (libsource (lib "eagle-import") (part "R-US_R1206"))
    )
    (comp (ref "R60")
      (value "20K")
      (footprint "eagle-import:RTRIM3103")
      (libsource (lib "eagle-import") (part "R-TRIMM3103"))
    )
    (comp (ref "R61")
      (value "20K")
      (footprint "eagle-import:R0603")
      (libsource (lib "eagle-import") (part "R-US_R0603"))
    )
    (comp (ref "R62")
      (value "0R11")
      (footprint "eagle-import:R1206")
      (libsource (lib "eagle-import") (part "R-US_R1206"))
    )
    (comp (ref "R63")
      (value "0R11")
      (footprint "eagle-import:R1206")
      (libsource (lib "eagle-import") (part "R-US_R1206"))
    )
    (comp (ref "R64")
      (value "20K")
      (footprint "eagle-import:RTRIM3103")
      (libsource (lib "eagle-import") (part "R-TRIMM3103"))
    )
    (comp (ref "R65")
      (value "20K")
      (footprint "eagle-import:R0603")
      (libsource (lib "eagle-import") (part "R-US_R0603"))
    )
    (comp (ref "R66")
      (value "0R11")
      (footprint "eagle-import:R1206")
      (libsource (lib "eagle-import") (part "R-US_R1206"))
    )
    (comp (ref "R67")
      (value "0R11")
      (footprint "eagle-import:R1206")
      (libsource (lib "eagle-import") (part "R-US_R1206"))
    )
    (comp (ref "R68")
      (value "20K")
      (footprint "eagle-import:RTRIM3103")
      (libsource (lib "eagle-import") (part "R-TRIMM3103"))
    )
    (comp (ref "R69")
      (value "20K")
      (footprint "eagle-import:R0603")
      (libsource (lib "eagle-import") (part "R-US_R0603"))
    )
    (comp (ref "RESET")
      (value "EVQQ2")
      (footprint "eagle-import:EVQQ2")
      (libsource (lib "eagle-import") (part "EVQQ2"))
    )
    (comp (ref "SJ1") (value "SJ") (footprint "eagle-import:SJ") (libsource (lib "eagle-import") (part "SJ")))
    (comp (ref "SJ2") (value "SJ") (footprint "eagle-import:SJ") (libsource (lib "eagle-import") (part "SJ")))
    (comp (ref "U1")
      (value "A4403")
      (footprint "eagle-import:QFN16-4X4")
      (libsource (lib "eagle-import") (part "A4403"))
    )
    (comp (ref "USB")
      (value "LEDCHIPLED_0805")
      (footprint "eagle-import:CHIPLED_0805")
      (libsource (lib "eagle-import") (part "LEDCHIPLED_0805"))
    )
    (comp (ref "VIN")
      (value "LEDCHIPLED_0805")
      (footprint "eagle-import:CHIPLED_0805")
      (libsource (lib "eagle-import") (part "LEDCHIPLED_0805"))
    )
    (comp (ref "X1")
      (value "USB-B_TH")
      (footprint "eagle-import:PN61729")
      (libsource (lib "eagle-import") (part "PN61729"))
    )
    (comp (ref "X2")
      (value "12MHz")
      (footprint "eagle-import:5.0X3.2_KX-9A")
      (libsource (lib "eagle-import") (part "CRYSTAL-4PIN"))
    )
    (comp (ref "X3")
      (value "KK-254-2")
      (footprint "eagle-import:MOLEX-KK-254-2")
      (libsource (lib "eagle-import") (part "KK-254-2"))
    )
    (comp (ref "X4")
      (value "KK-254-4")
      (footprint "eagle-import:MOLEX-KK-254-4")
      (libsource (lib "eagle-import") (part "KK-254-4"))
    )
    (comp (ref "X5")
      (value "KK-254-4")
      (footprint "eagle-import:MOLEX-KK-254-4")
      (libsource (lib "eagle-import") (part "KK-254-4"))
    )
    (comp (ref "X6")
      (value "KK-254-4")
      (footprint "eagle-import:MOLEX-KK-254-4")
      (libsource (lib "eagle-import") (part "KK-254-4"))
    )
    (comp (ref "X7")
      (value "KK-254-4")
      (footprint "eagle-import:MOLEX-KK-254-4")
      (libsource (lib "eagle-import") (part "KK-254-4"))
    )
    (comp (ref "X8")
      (value "KK-254-4")
      (footprint "eagle-import:MOLEX-KK-254-4")
      (libsource (lib "eagle-import") (part "KK-254-4"))
    )
    (comp (ref "X9")
      (value "KK-254-4")
      (footprint "eagle-import:MOLEX-KK-254-4")
      (libsource (lib "eagle-import") (part "KK-254-4"))
    )
    (comp (ref "X_STOP")
      (value "KK-254-3")
      (footprint "eagle-import:MOLEX-KK-254-3")
      (libsource (lib "eagle-import") (part "KK-254-3"))
    )
    (comp (ref "Y_STOP")
      (value "KK-254-3")
      (footprint "eagle-import:MOLEX-KK-254-3")
      (libsource (lib "eagle-import") (part "KK-254-3"))
    )
    (comp (ref "Z_STOP")
      (value "KK-254-3")
      (footprint "eagle-import:MOLEX-KK-254-3")
      (libsource (lib "eagle-import") (part "KK-254-3"))
    )
  )
  (nets
    (net (code "1") (name "+3V3") (class "Default")
      (node (ref "3V1") (pin "A") (pinfunction "A_A") (pintype "passive"))
      (node (ref "C111") (pin "1") (pinfunction "1_1") (pintype "passive"))
      (node (ref "C13") (pin "+") (pinfunction "+_+") (pintype "passive"))
      (node (ref "C14") (pin "1") (pinfunction "1_1") (pintype "passive"))
      (node (ref "C16") (pin "2") (pinfunction "2_2") (pintype "passive"))
      (node (ref "C17") (pin "2") (pinfunction "2_2") (pintype "passive"))
      (node (ref "C18") (pin "2") (pinfunction "2_2") (pintype "passive"))
      (node (ref "C19") (pin "2") (pinfunction "2_2") (pintype "passive"))
      (node (ref "C20") (pin "2") (pinfunction "2_2") (pintype "passive"))
      (node (ref "C21") (pin "2") (pinfunction "2_2") (pintype "passive"))
      (node (ref "C23") (pin "1") (pinfunction "1_1") (pintype "passive"))
      (node (ref "C25") (pin "1") (pinfunction "1_1") (pintype "passive"))
      (node (ref "C38") (pin "1") (pinfunction "1_1") (pintype "passive"))
      (node (ref "C39") (pin "1") (pinfunction "1_1") (pintype "passive"))
      (node (ref "C40") (pin "1") (pinfunction "1_1") (pintype "passive"))
      (node (ref "C44") (pin "1") (pinfunction "1_1") (pintype "passive"))
      (node (ref "C46") (pin "1") (pinfunction "1_1") (pintype "passive"))
      (node (ref "C59") (pin "1") (pinfunction "1_1") (pintype "passive"))
      (node (ref "C72") (pin "1") (pinfunction "1_1") (pintype "passive"))
      (node (ref "C85") (pin "1") (pinfunction "1_1") (pintype "passive"))
      (node (ref "C98") (pin "1") (pinfunction "1_1") (pintype "passive"))
      (node (ref "ERASE") (pin "1") (pinfunction "1_1") (pintype "passive"))
      (node (ref "IC1") (pin "2") (pinfunction "VO_2") (pintype "passive"))
      (node (ref "IC1") (pin "4") (pinfunction "VO_4") (pintype "passive"))
      (node (ref "IC10") (pin "8") (pinfunction "VCC_IO_8") (pintype "power_in"))
      (node (ref "IC11") (pin "14") (pinfunction "VCC_14") (pintype "power_in"))
      (node (ref "IC2") (pin "10") (pinfunction "VDDIN_10") (pintype "bidirectional"))
      (node (ref "IC2") (pin "27") (pinfunction "VDDIO-27_27") (pintype "bidirectional"))
      (node (ref "IC2") (pin "50") (pinfunction "VDDIO-50_50") (pintype "bidirectional"))
      (node (ref "IC2") (pin "69") (pinfunction "VDDIO-69_69") (pintype "bidirectional"))
      (node (ref "IC2") (pin "91") (pinfunction "VDDIO-91_91") (pintype "bidirectional"))
      (node (ref "IC2") (pin "98") (pinfunction "VDDIO-98_98") (pintype "bidirectional"))
      (node (ref "IC3") (pin "8") (pinfunction "VDD_8") (pintype "power_in"))
      (node (ref "IC4") (pin "14") (pinfunction "VCC_14") (pintype "power_in"))
      (node (ref "IC6") (pin "8") (pinfunction "VCC_IO_8") (pintype "power_in"))
      (node (ref "IC7") (pin "8") (pinfunction "VCC_IO_8") (pintype "power_in"))
      (node (ref "IC8") (pin "8") (pinfunction "VCC_IO_8") (pintype "power_in"))
      (node (ref "IC9") (pin "8") (pinfunction "VCC_IO_8") (pintype "power_in"))
      (node (ref "J1") (pin "P4") (pinfunction "VDD_P4") (pintype "power_in"))
      (node (ref "L4") (pin "2") (pinfunction "2_2") (pintype "passive"))
      (node (ref "L6") (pin "1") (pinfunction "1_1") (pintype "passive"))
      (node (ref "R16") (pin "2") (pinfunction "2_2") (pintype "passive"))
      (node (ref "R34") (pin "2") (pinfunction "2_2") (pintype "passive"))
      (node (ref "R35") (pin "2") (pinfunction "2_2") (pintype "passive"))
      (node (ref "SJ1") (pin "1") (pinfunction "1_1") (pintype "passive"))
      (node (ref "X_STOP") (pin "2") (pinfunction "S_2") (pintype "passive"))
      (node (ref "Y_STOP") (pin "2") (pinfunction "S_2") (pintype "passive"))
    )
    (net (code "2") (name "+5V") (class "Default")
      (node (ref "5V") (pin "A") (pinfunction "A_A") (pintype "passive"))
      (node (ref "C11") (pin "+") (pinfunction "+_+") (pintype "passive"))
      (node (ref "C12") (pin "1") (pinfunction "1_1") (pintype "passive"))
      (node (ref "C45") (pin "1") (pinfunction "1_1") (pintype "passive"))
      (node (ref "C47") (pin "1") (pinfunction "1_1") (pintype "passive"))
      (node (ref "C60") (pin "1") (pinfunction "1_1") (pintype "passive"))
      (node (ref "C73") (pin "1") (pinfunction "1_1") (pintype "passive"))
      (node (ref "C86") (pin "1") (pinfunction "1_1") (pintype "passive"))
      (node (ref "C99") (pin "1") (pinfunction "1_1") (pintype "passive"))
      (node (ref "EXP_2") (pin "10") (pinfunction "S_10") (pintype "passive"))
      (node (ref "IC1") (pin "3") (pinfunction "VI_3") (pintype "input"))
      (node (ref "IC10") (pin "26") (pinfunction "VCC_26") (pintype "power_in"))
      (node (ref "IC5") (pin "14") (pinfunction "VCC_14") (pintype "power_in"))
      (node (ref "IC6") (pin "26") (pinfunction "VCC_26") (pintype "power_in"))
      (node (ref "IC7") (pin "26") (pinfunction "VCC_26") (pintype "power_in"))
      (node (ref "IC8") (pin "26") (pinfunction "VCC_26") (pintype "power_in"))
      (node (ref "IC9") (pin "26") (pinfunction "VCC_26") (pintype "power_in"))
      (node (ref "L3") (pin "2") (pinfunction "2_2") (pintype "passive"))
      (node (ref "R53") (pin "2") (pinfunction "2_2") (pintype "passive"))
      (node (ref "R57") (pin "2") (pinfunction "2_2") (pintype "passive"))
      (node (ref "R61") (pin "2") (pinfunction "2_2") (pintype "passive"))
      (node (ref "R65") (pin "2") (pinfunction "2_2") (pintype "passive"))
      (node (ref "R69") (pin "2") (pinfunction "2_2") (pintype "passive"))
    )
    (net (code "3") (name "+12V") (class "Default")
      (node (ref "C101") (pin "2") (pinfunction "2_2") (pintype "passive"))
      (node (ref "C102") (pin "1") (pinfunction "1_1") (pintype "passive"))
      (node (ref "C104") (pin "+") (pinfunction "+_+") (pintype "passive"))
      (node (ref "C105") (pin "1") (pinfunction "1_1") (pintype "passive"))
      (node (ref "C106") (pin "1") (pinfunction "1_1") (pintype "passive"))
      (node (ref "C49") (pin "2") (pinfunction "2_2") (pintype "passive"))
      (node (ref "C50") (pin "1") (pinfunction "1_1") (pintype "passive"))
      (node (ref "C52") (pin "+") (pinfunction "+_+") (pintype "passive"))
      (node (ref "C53") (pin "1") (pinfunction "1_1") (pintype "passive"))
      (node (ref "C54") (pin "1") (pinfunction "1_1") (pintype "passive"))
      (node (ref "C62") (pin "2") (pinfunction "2_2") (pintype "passive"))
      (node (ref "C63") (pin "1") (pinfunction "1_1") (pintype "passive"))
      (node (ref "C65") (pin "+") (pinfunction "+_+") (pintype "passive"))
      (node (ref "C66") (pin "1") (pinfunction "1_1") (pintype "passive"))
      (node (ref "C67") (pin "1") (pinfunction "1_1") (pintype "passive"))
      (node (ref "C75") (pin "2") (pinfunction "2_2") (pintype "passive"))
      (node (ref "C76") (pin "1") (pinfunction "1_1") (pintype "passive"))
      (node (ref "C78") (pin "+") (pinfunction "+_+") (pintype "passive"))
      (node (ref "C79") (pin "1") (pinfunction "1_1") (pintype "passive"))
      (node (ref "C80") (pin "1") (pinfunction "1_1") (pintype "passive"))
      (node (ref "C88") (pin "2") (pinfunction "2_2") (pintype "passive"))
      (node (ref "C89") (pin "1") (pinfunction "1_1") (pintype "passive"))
      (node (ref "C91") (pin "+") (pinfunction "+_+") (pintype "passive"))
      (node (ref "C92") (pin "1") (pinfunction "1_1") (pintype "passive"))
      (node (ref "C93") (pin "1") (pinfunction "1_1") (pintype "passive"))
      (node (ref "D1") (pin "A") (pinfunction "A_A") (pintype "passive"))
      (node (ref "F2") (pin "1") (pinfunction "1_1") (pintype "passive"))
      (node (ref "F3") (pin "1") (pinfunction "1_1") (pintype "passive"))
      (node (ref "FAN1") (pin "1") (pinfunction "S_1") (pintype "passive"))
      (node (ref "FAN2") (pin "1") (pinfunction "S_1") (pintype "passive"))
      (node (ref "FAN3") (pin "1") (pinfunction "S_1") (pintype "passive"))
      (node (ref "FAN4") (pin "1") (pinfunction "S_1") (pintype "passive"))
      (node (ref "IC10") (pin "16") (pinfunction "VS_16") (pintype "power_in"))
      (node (ref "IC10") (pin "30") (pinfunction "VSA_30") (pintype "power_in"))
      (node (ref "IC10") (pin "31") (pinfunction "VS_31") (pintype "power_in"))
      (node (ref "IC6") (pin "16") (pinfunction "VS_16") (pintype "power_in"))
      (node (ref "IC6") (pin "30") (pinfunction "VSA_30") (pintype "power_in"))
      (node (ref "IC6") (pin "31") (pinfunction "VS_31") (pintype "power_in"))
      (node (ref "IC7") (pin "16") (pinfunction "VS_16") (pintype "power_in"))
      (node (ref "IC7") (pin "30") (pinfunction "VSA_30") (pintype "power_in"))
      (node (ref "IC7") (pin "31") (pinfunction "VS_31") (pintype "power_in"))
      (node (ref "IC8") (pin "16") (pinfunction "VS_16") (pintype "power_in"))
      (node (ref "IC8") (pin "30") (pinfunction "VSA_30") (pintype "power_in"))
      (node (ref "IC8") (pin "31") (pinfunction "VS_31") (pintype "power_in"))
      (node (ref "IC9") (pin "16") (pinfunction "VS_16") (pintype "power_in"))
      (node (ref "IC9") (pin "30") (pinfunction "VSA_30") (pintype "power_in"))
      (node (ref "IC9") (pin "31") (pinfunction "VS_31") (pintype "power_in"))
      (node (ref "PWRIN") (pin "1") (pinfunction "1_1") (pintype "passive"))
      (node (ref "R1") (pin "2") (pinfunction "2_2") (pintype "passive"))
      (node (ref "R48") (pin "2") (pinfunction "2_2") (pintype "passive"))
      (node (ref "R49") (pin "2") (pinfunction "2_2") (pintype "passive"))
      (node (ref "SJ2") (pin "1") (pinfunction "1_1") (pintype "passive"))
      (node (ref "VIN") (pin "A") (pinfunction "A_A") (pintype "passive"))
    )
    (net (code "4") (name "/ADVREF") (class "Default")
      (node (ref "C24") (pin "1") (pinfunction "1_1") (pintype "passive"))
      (node (ref "IC2") (pin "1") (pinfunction "ADVREF_1") (pintype "bidirectional"))
      (node (ref "L4") (pin "1") (pinfunction "1_1") (pintype "passive"))
      (node (ref "R39") (pin "2") (pinfunction "2_2") (pintype "passive"))
      (node (ref "R40") (pin "2") (pinfunction "2_2") (pintype "passive"))
      (node (ref "R41") (pin "2") (pinfunction "2_2") (pintype "passive"))
    )
    (net (code "5") (name "/BED") (class "Default")
      (node (ref "IC2") (pin "86") (pinfunction "PC22_86") (pintype "bidirectional"))
      (node (ref "X3") (pin "1") (pinfunction "S_1") (pintype "passive"))
    )
    (net (code "6") (name "/E1_DIR") (class "Default")
      (node (ref "IC2") (pin "51") (pinfunction "TDI/PB4_51") (pintype "bidirectional"))
      (node (ref "IC9") (pin "7") (pinfunction "REFR_DIR_7") (pintype "bidirectional"))
    )
    (net (code "7") (name "/E1_EN") (class "Default")
      (node (ref "IC2") (pin "55") (pinfunction "PA4/PGMNCMD_55") (pintype "bidirectional"))
      (node (ref "IC9") (pin "2") (pinfunction "CSN_CFG3_2") (pintype "bidirectional"))
    )
    (net (code "8") (name "/E1_STEP") (class "Default")
      (node (ref "IC2") (pin "54") (pinfunction "PC28_54") (pintype "bidirectional"))
      (node (ref "IC9") (pin "6") (pinfunction "REFL_STEP_6") (pintype "bidirectional"))
    )
    (net (code "9") (name "/E2_DIR") (class "Default")
      (node (ref "IC10") (pin "7") (pinfunction "REFR_DIR_7") (pintype "bidirectional"))
      (node (ref "IC2") (pin "62") (pinfunction "PC9_62") (pintype "bidirectional"))
    )
    (net (code "10") (name "/E2_EN") (class "Default")
      (node (ref "IC10") (pin "2") (pinfunction "CSN_CFG3_2") (pintype "bidirectional"))
      (node (ref "IC2") (pin "66") (pinfunction "PA3_66") (pintype "bidirectional"))
    )
    (net (code "11") (name "/E2_STEP") (class "Default")
      (node (ref "IC10") (pin "6") (pinfunction "REFL_STEP_6") (pintype "bidirectional"))
      (node (ref "IC2") (pin "65") (pinfunction "PC10_65") (pintype "bidirectional"))
    )
    (net (code "12") (name "/ENN") (class "Default")
      (node (ref "IC10") (pin "22") (pinfunction "DRV_ENN_CFG6_22") (pintype "bidirectional"))
      (node (ref "IC2") (pin "71") (pinfunction "PC14_71") (pintype "bidirectional"))
      (node (ref "IC6") (pin "22") (pinfunction "DRV_ENN_CFG6_22") (pintype "bidirectional"))
      (node (ref "IC7") (pin "22") (pinfunction "DRV_ENN_CFG6_22") (pintype "bidirectional"))
      (node (ref "IC8") (pin "22") (pinfunction "DRV_ENN_CFG6_22") (pintype "bidirectional"))
      (node (ref "IC9") (pin "22") (pinfunction "DRV_ENN_CFG6_22") (pintype "bidirectional"))
    )
    (net (code "13") (name "/ESP_DATA_RDY") (class "Default")
      (node (ref "IC2") (pin "13") (pinfunction "PC26_13") (pintype "bidirectional"))
      (node (ref "R25") (pin "1") (pinfunction "1_1") (pintype "passive"))
    )
    (net (code "14") (name "/ESP_EN") (class "Default")
      (node (ref "ESP1") (pin "3") (pinfunction "CH_PD_3") (pintype "input"))
      (node (ref "IC2") (pin "32") (pinfunction "PC6_32") (pintype "bidirectional"))
      (node (ref "R17") (pin "1") (pinfunction "1_1") (pintype "passive"))
    )
    (net (code "15") (name "/ESP_MISO") (class "Default")
      (node (ref "IC2") (pin "41") (pinfunction "PA12/PGMD0_41") (pintype "bidirectional"))
      (node (ref "R20") (pin "2") (pinfunction "2_2") (pintype "passive"))
    )
    (net (code "16") (name "/ESP_MOSI") (class "Default")
      (node (ref "IC2") (pin "33") (pinfunction "PA13/PGMD1_33") (pintype "bidirectional"))
      (node (ref "R21") (pin "2") (pinfunction "2_2") (pintype "passive"))
    )
    (net (code "17") (name "/ESP_NPCS0") (class "Default")
      (node (ref "IC2") (pin "42") (pinfunction "PA11/PGMM3_42") (pintype "bidirectional"))
      (node (ref "R26") (pin "1") (pinfunction "1_1") (pintype "passive"))
    )
    (net (code "18") (name "/ESP_RESET") (class "Default")
      (node (ref "IC2") (pin "43") (pinfunction "PC2_43") (pintype "bidirectional"))
      (node (ref "R18") (pin "1") (pinfunction "1_1") (pintype "passive"))
    )
    (net (code "19") (name "/ESP_SCK") (class "Default")
      (node (ref "IC2") (pin "31") (pinfunction "PA14/PGMD2_31") (pintype "bidirectional"))
      (node (ref "R19") (pin "2") (pinfunction "2_2") (pintype "passive"))
    )
    (net (code "20") (name "/ESP_URXD") (class "Default")
      (node (ref "IC2") (pin "46") (pinfunction "PA9/PGMM1_46") (pintype "bidirectional"))
      (node (ref "R23") (pin "1") (pinfunction "1_1") (pintype "passive"))
    )
    (net (code "21") (name "/ESP_UTXD") (class "Default")
      (node (ref "IC2") (pin "44") (pinfunction "PA10/PGMM2_44") (pintype "bidirectional"))
      (node (ref "R24") (pin "1") (pinfunction "1_1") (pintype "passive"))
    )
    (net (code "22") (name "/EXT1") (class "Default")
      (node (ref "IC2") (pin "24") (pinfunction "PA20/PGMD8/AD3_24") (pintype "bidirectional"))
      (node (ref "R46") (pin "1") (pinfunction "1_1") (pintype "passive"))
    )
    (net (code "23") (name "/EXT2") (class "Default")
      (node (ref "IC2") (pin "19") (pinfunction "PC15/AD11_19") (pintype "bidirectional"))
      (node (ref "R47") (pin "1") (pinfunction "1_1") (pintype "passive"))
    )
    (net (code "24") (name "/FAN_E1") (class "Default")
      (node (ref "IC2") (pin "40") (pinfunction "PC3_40") (pintype "bidirectional"))
      (node (ref "R42") (pin "1") (pinfunction "1_1") (pintype "passive"))
    )
    (net (code "25") (name "/FAN_E2") (class "Default")
      (node (ref "IC2") (pin "25") (pinfunction "PC0_25") (pintype "bidirectional"))
      (node (ref "R43") (pin "1") (pinfunction "1_1") (pintype "passive"))
    )
    (net (code "26") (name "/FAN_MOBO") (class "Default")
      (node (ref "IC2") (pin "14") (pinfunction "PA18/PGMD6/AD1_14") (pintype "bidirectional"))
      (node (ref "R44") (pin "1") (pinfunction "1_1") (pintype "passive"))
    )
    (net (code "27") (name "/FAN_PART") (class "Default")
      (node (ref "IC2") (pin "21") (pinfunction "PC13/AD10_21") (pintype "bidirectional"))
      (node (ref "R45") (pin "1") (pinfunction "1_1") (pintype "passive"))
    )
    (net (code "28") (name "/LCD_BEEP") (class "Default")
      (node (ref "EXP_2") (pin "1") (pinfunction "S_1") (pintype "passive"))
      (node (ref "IC2") (pin "90") (pinfunction "PC23_90") (pintype "bidirectional"))
    )
    (net (code "29") (name "/LCD_CS") (class "Default")
      (node (ref "IC2") (pin "80") (pinfunction "PC19_80") (pintype "bidirectional"))
      (node (ref "IC5") (pin "13") (pinfunction "I1_13") (pintype "input"))
      (node (ref "IC5") (pin "2") (pinfunction "I1_2") (pintype "input"))
      (node (ref "IC5") (pin "4") (pinfunction "I0_4") (pintype "input"))
      (node (ref "IC5") (pin "5") (pinfunction "I1_5") (pintype "input"))
    )
    (net (code "30") (name "/LCD_ENC_A") (class "Default")
      (node (ref "EXP_1") (pin "5") (pinfunction "S_5") (pintype "passive"))
      (node (ref "IC2") (pin "83") (pinfunction "TCK/SWCLK/PB7_83") (pintype "bidirectional"))
    )
    (net (code "31") (name "/LCD_ENC_B") (class "Default")
      (node (ref "EXP_1") (pin "3") (pinfunction "S_3") (pintype "passive"))
      (node (ref "IC2") (pin "82") (pinfunction "PC20_82") (pintype "bidirectional"))
    )
    (net (code "32") (name "/LCD_ENC_SW") (class "Default")
      (node (ref "EXP_2") (pin "2") (pinfunction "S_2") (pintype "passive"))
      (node (ref "IC2") (pin "84") (pinfunction "PC21_84") (pintype "bidirectional"))
    )
    (net (code "33") (name "/LCD_MISO") (class "Default")
      (node (ref "IC2") (pin "53") (pinfunction "PA5/PGMRDY_53") (pintype "bidirectional"))
      (node (ref "IC4") (pin "8") (pinfunction "O_8") (pintype "tri_state"))
    )
    (net (code "34") (name "/LCD_MISO_BUF") (class "Default")
      (node (ref "EXP_1") (pin "1") (pinfunction "S_1") (pintype "passive"))
      (node (ref "IC4") (pin "9") (pinfunction "I_9") (pintype "input"))
    )
    (net (code "35") (name "/LCD_MOSI") (class "Default")
      (node (ref "IC2") (pin "52") (pinfunction "PB6/PGMNOE_52") (pintype "bidirectional"))
      (node (ref "IC4") (pin "2") (pinfunction "I_2") (pintype "input"))
      (node (ref "IC5") (pin "1") (pinfunction "I0_1") (pintype "input"))
    )
    (net (code "36") (name "/LCD_MOSI_BUF") (class "Default")
      (node (ref "EXP_2") (pin "3") (pinfunction "S_3") (pintype "passive"))
      (node (ref "IC5") (pin "3") (pinfunction "O_3") (pintype "output"))
    )
    (net (code "37") (name "/LCD_SCK") (class "Default")
      (node (ref "IC2") (pin "67") (pinfunction "PA2/PGMEN2_67") (pintype "bidirectional"))
      (node (ref "IC4") (pin "5") (pinfunction "I_5") (pintype "input"))
      (node (ref "IC5") (pin "12") (pinfunction "I0_12") (pintype "input"))
    )
    (net (code "38") (name "/LCD_SCK_BUF") (class "Default")
      (node (ref "EXP_2") (pin "5") (pinfunction "S_5") (pintype "passive"))
      (node (ref "IC5") (pin "11") (pinfunction "O_11") (pintype "output"))
    )
    (net (code "39") (name "/LCD_SD_CS") (class "Default")
      (node (ref "EXP_1") (pin "4") (pinfunction "S_4") (pintype "passive"))
      (node (ref "IC2") (pin "99") (pinfunction "PB14/DAC1_99") (pintype "bidirectional"))
      (node (ref "IC4") (pin "10") (pinfunction "OE_10") (pintype "input"))
    )
    (net (code "40") (name "/MCCDA") (class "Default")
      (node (ref "IC2") (pin "59") (pinfunction "PA28_59") (pintype "bidirectional"))
      (node (ref "R29") (pin "1") (pinfunction "1_1") (pintype "passive"))
    )
    (net (code "41") (name "/MCCK") (class "Default")
      (node (ref "IC2") (pin "63") (pinfunction "PA29_63") (pintype "bidirectional"))
      (node (ref "R30") (pin "1") (pinfunction "1_1") (pintype "passive"))
    )
    (net (code "42") (name "/MCDA0") (class "Default")
      (node (ref "IC2") (pin "64") (pinfunction "PA30_64") (pintype "bidirectional"))
      (node (ref "R28") (pin "1") (pinfunction "1_1") (pintype "passive"))
    )
    (net (code "43") (name "/MCDA1") (class "Default")
      (node (ref "IC2") (pin "81") (pinfunction "PA31_81") (pintype "bidirectional"))
      (node (ref "R32") (pin "1") (pinfunction "1_1") (pintype "passive"))
    )
    (net (code "44") (name "/MCDA2") (class "Default")
      (node (ref "IC2") (pin "39") (pinfunction "PA26/PGMD14_39") (pintype "bidirectional"))
      (node (ref "R33") (pin "1") (pinfunction "1_1") (pintype "passive"))
    )
    (net (code "45") (name "/MCDA3") (class "Default")
      (node (ref "IC2") (pin "57") (pinfunction "PA27/PGMD15_57") (pintype "bidirectional"))
      (node (ref "R31") (pin "1") (pinfunction "1_1") (pintype "passive"))
    )
    (net (code "46") (name "/MOT_MISO") (class "Default")
      (node (ref "IC10") (pin "5") (pinfunction "SDO_NAO_CFG0_5") (pintype "bidirectional"))
      (node (ref "IC2") (pin "15") (pinfunction "PA21/PGMD9/AD8_15") (pintype "bidirectional"))
      (node (ref "IC6") (pin "5") (pinfunction "SDO_NAO_CFG0_5") (pintype "bidirectional"))
      (node (ref "IC7") (pin "5") (pinfunction "SDO_NAO_CFG0_5") (pintype "bidirectional"))
      (node (ref "IC8") (pin "5") (pinfunction "SDO_NAO_CFG0_5") (pintype "bidirectional"))
      (node (ref "IC9") (pin "5") (pinfunction "SDO_NAO_CFG0_5") (pintype "bidirectional"))
    )
    (net (code "47") (name "/MOT_MOSI") (class "Default")
      (node (ref "IC10") (pin "4") (pinfunction "SDI_NAI_CFG1_4") (pintype "bidirectional"))
      (node (ref "IC2") (pin "20") (pinfunction "PA22/PGMD10/AD9_20") (pintype "bidirectional"))
      (node (ref "IC6") (pin "4") (pinfunction "SDI_NAI_CFG1_4") (pintype "bidirectional"))
      (node (ref "IC7") (pin "4") (pinfunction "SDI_NAI_CFG1_4") (pintype "bidirectional"))
      (node (ref "IC8") (pin "4") (pinfunction "SDI_NAI_CFG1_4") (pintype "bidirectional"))
      (node (ref "IC9") (pin "4") (pinfunction "SDI_NAI_CFG1_4") (pintype "bidirectional"))
    )
    (net (code "48") (name "/MOT_SCK") (class "Default")
      (node (ref "IC10") (pin "3") (pinfunction "SCK_CFG2_3") (pintype "bidirectional"))
      (node (ref "IC2") (pin "22") (pinfunction "PA23/PGMD11_22") (pintype "bidirectional"))
      (node (ref "IC6") (pin "3") (pinfunction "SCK_CFG2_3") (pintype "bidirectional"))
      (node (ref "IC7") (pin "3") (pinfunction "SCK_CFG2_3") (pintype "bidirectional"))
      (node (ref "IC8") (pin "3") (pinfunction "SCK_CFG2_3") (pintype "bidirectional"))
      (node (ref "IC9") (pin "3") (pinfunction "SCK_CFG2_3") (pintype "bidirectional"))
    )
    (net (code "49") (name "/PWR_FAIL_DET2") (class "Default")
      (node (ref "C1") (pin "1") (pinfunction "1_1") (pintype "passive"))
      (node (ref "IC2") (pin "6") (pinfunction "PC30/AD14_6") (pintype "bidirectional"))
      (node (ref "R1") (pin "1") (pinfunction "1_1") (pintype "passive"))
      (node (ref "R2") (pin "2") (pinfunction "2_2") (pintype "passive"))
    )
    (net (code "50") (name "/RESET") (class "Default")
      (node (ref "C35") (pin "1") (pinfunction "1_1") (pintype "passive"))
      (node (ref "IC2") (pin "60") (pinfunction "NRST_60") (pintype "bidirectional"))
      (node (ref "R16") (pin "1") (pinfunction "1_1") (pintype "passive"))
      (node (ref "RESET") (pin "A") (pinfunction "P_A") (pintype "passive"))
    )
    (net (code "51") (name "/SAM_TFR_RDY") (class "Default")
      (node (ref "ESP1") (pin "14") (pinfunction "GPIO4_14") (pintype "bidirectional"))
      (node (ref "IC2") (pin "49") (pinfunction "PA7/XIN32/PGMNVALID_49") (pintype "bidirectional"))
    )
    (net (code "52") (name "/SD_CD") (class "Default")
      (node (ref "IC2") (pin "58") (pinfunction "PC8_58") (pintype "bidirectional"))
      (node (ref "R27") (pin "1") (pinfunction "1_1") (pintype "passive"))
    )
    (net (code "53") (name "/SG_TST") (class "Default")
      (node (ref "IC11") (pin "11") (pinfunction "O_11") (pintype "output"))
      (node (ref "IC2") (pin "72") (pinfunction "PA1/PGMEN1_72") (pintype "bidirectional"))
    )
    (net (code "54") (name "/SG_TST_E1") (class "Default")
      (node (ref "IC11") (pin "5") (pinfunction "I1_5") (pintype "input"))
      (node (ref "IC9") (pin "21") (pinfunction "SWP_DIAG1_21") (pintype "bidirectional"))
    )
    (net (code "55") (name "/SG_TST_E2") (class "Default")
      (node (ref "IC10") (pin "21") (pinfunction "SWP_DIAG1_21") (pintype "bidirectional"))
      (node (ref "IC11") (pin "9") (pinfunction "I0_9") (pintype "input"))
    )
    (net (code "56") (name "/SG_TST_X") (class "Default")
      (node (ref "IC11") (pin "1") (pinfunction "I0_1") (pintype "input"))
      (node (ref "IC6") (pin "21") (pinfunction "SWP_DIAG1_21") (pintype "bidirectional"))
    )
    (net (code "57") (name "/SG_TST_Y") (class "Default")
      (node (ref "IC11") (pin "2") (pinfunction "I1_2") (pintype "input"))
      (node (ref "IC7") (pin "21") (pinfunction "SWP_DIAG1_21") (pintype "bidirectional"))
    )
    (net (code "58") (name "/SG_TST_Z") (class "Default")
      (node (ref "IC11") (pin "4") (pinfunction "I0_4") (pintype "input"))
      (node (ref "IC8") (pin "21") (pinfunction "SWP_DIAG1_21") (pintype "bidirectional"))
    )
    (net (code "59") (name "/T_BED") (class "Default")
      (node (ref "C43") (pin "1") (pinfunction "1_1") (pintype "passive"))
      (node (ref "IC2") (pin "5") (pinfunction "PB1/AD5_5") (pintype "bidirectional"))
      (node (ref "R36") (pin "1") (pinfunction "1_1") (pintype "passive"))
    )
    (net (code "60") (name "/T_EXT1") (class "Default")
      (node (ref "C42") (pin "1") (pinfunction "1_1") (pintype "passive"))
      (node (ref "IC2") (pin "3") (pinfunction "PB0/AD4_3") (pintype "bidirectional"))
      (node (ref "R37") (pin "1") (pinfunction "1_1") (pintype "passive"))
    )
    (net (code "61") (name "/T_EXT2") (class "Default")
      (node (ref "C41") (pin "1") (pinfunction "1_1") (pintype "passive"))
      (node (ref "IC2") (pin "4") (pinfunction "PC29/AD13_4") (pintype "bidirectional"))
      (node (ref "R38") (pin "1") (pinfunction "1_1") (pintype "passive"))
    )
    (net (code "62") (name "/USB_N") (class "Default")
      (node (ref "D3") (pin "3") (pinfunction "3_3") (pintype "bidirectional"))
      (node (ref "IC2") (pin "88") (pinfunction "DDM/PB10_88") (pintype "bidirectional"))
      (node (ref "X1") (pin "2") (pinfunction "2_2") (pintype "bidirectional"))
    )
    (net (code "63") (name "/USB_P") (class "Default")
      (node (ref "D3") (pin "2") (pinfunction "2_2") (pintype "bidirectional"))
      (node (ref "IC2") (pin "89") (pinfunction "DDP/PB11_89") (pintype "bidirectional"))
      (node (ref "X1") (pin "3") (pinfunction "3_3") (pintype "bidirectional"))
    )
    (net (code "64") (name "/USB_PWR_MON") (class "Default")
      (node (ref "C15") (pin "2") (pinfunction "2_2") (pintype "passive"))
      (node (ref "IC2") (pin "68") (pinfunction "PC11_68") (pintype "bidirectional"))
      (node (ref "R12") (pin "2") (pinfunction "2_2") (pintype "passive"))
      (node (ref "R13") (pin "1") (pinfunction "1_1") (pintype "passive"))
    )
    (net (code "65") (name "/VBUS") (class "Default")
      (node (ref "D3") (pin "4") (pinfunction "4_4") (pintype "bidirectional"))
      (node (ref "R12") (pin "1") (pinfunction "1_1") (pintype "passive"))
      (node (ref "USB") (pin "A") (pinfunction "A_A") (pintype "passive"))
      (node (ref "X1") (pin "1") (pinfunction "1_1") (pintype "bidirectional"))
    )
    (net (code "66") (name "/VREF_MON") (class "Default")
      (node (ref "IC2") (pin "12") (pinfunction "PA17/PGMD5/AD0_12") (pintype "bidirectional"))
    )
    (net (code "67") (name "/VSSA") (class "Default")
      (node (ref "BED") (pin "2") (pinfunction "S_2") (pintype "passive"))
      (node (ref "C22") (pin "1") (pinfunction "1_1") (pintype "passive"))
      (node (ref "EXT1") (pin "2") (pinfunction "S_2") (pintype "passive"))
      (node (ref "EXT2") (pin "2") (pinfunction "S_2") (pintype "passive"))
      (node (ref "F1") (pin "1") (pinfunction "1_1") (pintype "passive"))
      (node (ref "R14") (pin "2") (pinfunction "2_2") (pintype "passive"))
    )
    (net (code "68") (name "/VSSA_MON") (class "Default")
      (node (ref "IC2") (pin "18") (pinfunction "PA19/PGMD7/AD2_18") (pintype "bidirectional"))
      (node (ref "R14") (pin "1") (pinfunction "1_1") (pintype "passive"))
    )
    (net (code "69") (name "/X_DIR") (class "Default")
      (node (ref "IC2") (pin "28") (pinfunction "PA16/PGMD4_28") (pintype "bidirectional"))
      (node (ref "IC6") (pin "7") (pinfunction "REFR_DIR_7") (pintype "bidirectional"))
    )
    (net (code "70") (name "/X_EN") (class "Default")
      (node (ref "IC2") (pin "30") (pinfunction "PA15/PGMD3_30") (pintype "bidirectional"))
      (node (ref "IC6") (pin "2") (pinfunction "CSN_CFG3_2") (pintype "bidirectional"))
    )
    (net (code "71") (name "/X_STEP") (class "Default")
      (node (ref "IC2") (pin "29") (pinfunction "PC7_29") (pintype "bidirectional"))
      (node (ref "IC6") (pin "6") (pinfunction "REFL_STEP_6") (pintype "bidirectional"))
    )
    (net (code "72") (name "/X_STOP") (class "Default")
      (node (ref "IC2") (pin "73") (pinfunction "PC16_73") (pintype "bidirectional"))
      (node (ref "X_STOP") (pin "1") (pinfunction "S_1") (pintype "passive"))
    )
    (net (code "73") (name "/Y_DIR") (class "Default")
      (node (ref "IC2") (pin "34") (pinfunction "PA24/PGMD12_34") (pintype "bidirectional"))
      (node (ref "IC7") (pin "7") (pinfunction "REFR_DIR_7") (pintype "bidirectional"))
    )
    (net (code "74") (name "/Y_EN") (class "Default")
      (node (ref "IC2") (pin "37") (pinfunction "PC4_37") (pintype "bidirectional"))
      (node (ref "IC7") (pin "2") (pinfunction "CSN_CFG3_2") (pintype "bidirectional"))
    )
    (net (code "75") (name "/Y_STEP") (class "Default")
      (node (ref "IC2") (pin "35") (pinfunction "PC5_35") (pintype "bidirectional"))
      (node (ref "IC7") (pin "6") (pinfunction "REFL_STEP_6") (pintype "bidirectional"))
    )
    (net (code "76") (name "/Y_STOP") (class "Default")
      (node (ref "IC2") (pin "74") (pinfunction "PA0/PGMEN0_74") (pintype "bidirectional"))
      (node (ref "Y_STOP") (pin "1") (pinfunction "S_1") (pintype "passive"))
    )
    (net (code "77") (name "/Z_DIR") (class "Default")
      (node (ref "IC2") (pin "38") (pinfunction "PA25/PGMD13_38") (pintype "bidirectional"))
      (node (ref "IC8") (pin "7") (pinfunction "REFR_DIR_7") (pintype "bidirectional"))
    )
    (net (code "78") (name "/Z_EN") (class "Default")
      (node (ref "IC2") (pin "48") (pinfunction "PA8/XOUT32/PGMM0_48") (pintype "bidirectional"))
      (node (ref "IC8") (pin "2") (pinfunction "CSN_CFG3_2") (pintype "bidirectional"))
    )
    (net (code "79") (name "/Z_STEP") (class "Default")
      (node (ref "IC2") (pin "47") (pinfunction "PC1_47") (pintype "bidirectional"))
      (node (ref "IC8") (pin "6") (pinfunction "REFL_STEP_6") (pintype "bidirectional"))
    )
    (net (code "80") (name "/Z_STOP") (class "Default")
      (node (ref "IC2") (pin "75") (pinfunction "PC17_75") (pintype "bidirectional"))
      (node (ref "IC3") (pin "6") (pinfunction "OUT_6") (pintype "output"))
    )
    (net (code "81") (name "/Z_STOP_IN") (class "Default")
      (node (ref "IC3") (pin "2") (pinfunction "A1_2") (pintype "input"))
      (node (ref "Z_STOP") (pin "1") (pinfunction "S_1") (pintype "passive"))
    )
    (net (code "82") (name "GND") (class "Default")
      (node (ref "C1") (pin "2") (pinfunction "2_2") (pintype "passive"))
      (node (ref "C100") (pin "2") (pinfunction "2_2") (pintype "passive"))
      (node (ref "C101") (pin "1") (pinfunction "1_1") (pintype "passive"))
      (node (ref "C104") (pin "-") (pinfunction "-_-") (pintype "passive"))
      (node (ref "C105") (pin "2") (pinfunction "2_2") (pintype "passive"))
      (node (ref "C106") (pin "2") (pinfunction "2_2") (pintype "passive"))
      (node (ref "C107") (pin "2") (pinfunction "2_2") (pintype "passive"))
      (node (ref "C108") (pin "2") (pinfunction "2_2") (pintype "passive"))
      (node (ref "C109") (pin "2") (pinfunction "2_2") (pintype "passive"))
      (node (ref "C11") (pin "-") (pinfunction "-_-") (pintype "passive"))
      (node (ref "C110") (pin "2") (pinfunction "2_2") (pintype "passive"))
      (node (ref "C111") (pin "2") (pinfunction "2_2") (pintype "passive"))
      (node (ref "C12") (pin "2") (pinfunction "2_2") (pintype "passive"))
      (node (ref "C13") (pin "-") (pinfunction "-_-") (pintype "passive"))
      (node (ref "C14") (pin "2") (pinfunction "2_2") (pintype "passive"))
      (node (ref "C15") (pin "1") (pinfunction "1_1") (pintype "passive"))
      (node (ref "C16") (pin "1") (pinfunction "1_1") (pintype "passive"))
      (node (ref "C17") (pin "1") (pinfunction "1_1") (pintype "passive"))
      (node (ref "C18") (pin "1") (pinfunction "1_1") (pintype "passive"))
      (node (ref "C19") (pin "1") (pinfunction "1_1") (pintype "passive"))
      (node (ref "C2") (pin "2") (pinfunction "2_2") (pintype "passive"))
      (node (ref "C20") (pin "1") (pinfunction "1_1") (pintype "passive"))
      (node (ref "C21") (pin "1") (pinfunction "1_1") (pintype "passive"))
      (node (ref "C22") (pin "2") (pinfunction "2_2") (pintype "passive"))
      (node (ref "C23") (pin "2") (pinfunction "2_2") (pintype "passive"))
      (node (ref "C24") (pin "2") (pinfunction "2_2") (pintype "passive"))
      (node (ref "C25") (pin "2") (pinfunction "2_2") (pintype "passive"))
      (node (ref "C26") (pin "2") (pinfunction "2_2") (pintype "passive"))
      (node (ref "C27") (pin "2") (pinfunction "2_2") (pintype "passive"))
      (node (ref "C28") (pin "2") (pinfunction "2_2") (pintype "passive"))
      (node (ref "C29") (pin "2") (pinfunction "2_2") (pintype "passive"))
      (node (ref "C3") (pin "-") (pinfunction "-_-") (pintype "passive"))
      (node (ref "C30") (pin "2") (pinfunction "2_2") (pintype "passive"))
      (node (ref "C31") (pin "2") (pinfunction "2_2") (pintype "passive"))
      (node (ref "C32") (pin "2") (pinfunction "2_2") (pintype "passive"))
      (node (ref "C33") (pin "2") (pinfunction "2_2") (pintype "passive"))
      (node (ref "C34") (pin "2") (pinfunction "2_2") (pintype "passive"))
      (node (ref "C35") (pin "2") (pinfunction "2_2") (pintype "passive"))
      (node (ref "C36") (pin "2") (pinfunction "2_2") (pintype "passive"))
      (node (ref "C37") (pin "2") (pinfunction "2_2") (pintype "passive"))
      (node (ref "C38") (pin "2") (pinfunction "2_2") (pintype "passive"))
      (node (ref "C39") (pin "2") (pinfunction "2_2") (pintype "passive"))
      (node (ref "C4") (pin "2") (pinfunction "2_2") (pintype "passive"))
      (node (ref "C40") (pin "2") (pinfunction "2_2") (pintype "passive"))
      (node (ref "C41") (pin "2") (pinfunction "2_2") (pintype "passive"))
      (node (ref "C42") (pin "2") (pinfunction "2_2") (pintype "passive"))
      (node (ref "C43") (pin "2") (pinfunction "2_2") (pintype "passive"))
      (node (ref "C44") (pin "2") (pinfunction "2_2") (pintype "passive"))
      (node (ref "C45") (pin "2") (pinfunction "2_2") (pintype "passive"))
      (node (ref "C46") (pin "2") (pinfunction "2_2") (pintype "passive"))
      (node (ref "C47") (pin "2") (pinfunction "2_2") (pintype "passive"))
      (node (ref "C48") (pin "2") (pinfunction "2_2") (pintype "passive"))
      (node (ref "C49") (pin "1") (pinfunction "1_1") (pintype "passive"))
      (node (ref "C5") (pin "-") (pinfunction "-_-") (pintype "passive"))
      (node (ref "C52") (pin "-") (pinfunction "-_-") (pintype "passive"))
      (node (ref "C53") (pin "2") (pinfunction "2_2") (pintype "passive"))
      (node (ref "C54") (pin "2") (pinfunction "2_2") (pintype "passive"))
      (node (ref "C55") (pin "2") (pinfunction "2_2") (pintype "passive"))
      (node (ref "C56") (pin "2") (pinfunction "2_2") (pintype "passive"))
      (node (ref "C57") (pin "2") (pinfunction "2_2") (pintype "passive"))
      (node (ref "C58") (pin "2") (pinfunction "2_2") (pintype "passive"))
      (node (ref "C59") (pin "2") (pinfunction "2_2") (pintype "passive"))
      (node (ref "C6") (pin "2") (pinfunction "2_2") (pintype "passive"))
      (node (ref "C60") (pin "2") (pinfunction "2_2") (pintype "passive"))
      (node (ref "C61") (pin "2") (pinfunction "2_2") (pintype "passive"))
      (node (ref "C62") (pin "1") (pinfunction "1_1") (pintype "passive"))
      (node (ref "C65") (pin "-") (pinfunction "-_-") (pintype "passive"))
      (node (ref "C66") (pin "2") (pinfunction "2_2") (pintype "passive"))
      (node (ref "C67") (pin "2") (pinfunction "2_2") (pintype "passive"))
      (node (ref "C68") (pin "2") (pinfunction "2_2") (pintype "passive"))
      (node (ref "C69") (pin "2") (pinfunction "2_2") (pintype "passive"))
      (node (ref "C70") (pin "2") (pinfunction "2_2") (pintype "passive"))
      (node (ref "C71") (pin "2") (pinfunction "2_2") (pintype "passive"))
      (node (ref "C72") (pin "2") (pinfunction "2_2") (pintype "passive"))
      (node (ref "C73") (pin "2") (pinfunction "2_2") (pintype "passive"))
      (node (ref "C74") (pin "2") (pinfunction "2_2") (pintype "passive"))
      (node (ref "C75") (pin "1") (pinfunction "1_1") (pintype "passive"))
      (node (ref "C78") (pin "-") (pinfunction "-_-") (pintype "passive"))
      (node (ref "C79") (pin "2") (pinfunction "2_2") (pintype "passive"))
      (node (ref "C8") (pin "2") (pinfunction "2_2") (pintype "passive"))
      (node (ref "C80") (pin "2") (pinfunction "2_2") (pintype "passive"))
      (node (ref "C81") (pin "2") (pinfunction "2_2") (pintype "passive"))
      (node (ref "C82") (pin "2") (pinfunction "2_2") (pintype "passive"))
      (node (ref "C83") (pin "2") (pinfunction "2_2") (pintype "passive"))
      (node (ref "C84") (pin "2") (pinfunction "2_2") (pintype "passive"))
      (node (ref "C85") (pin "2") (pinfunction "2_2") (pintype "passive"))
      (node (ref "C86") (pin "2") (pinfunction "2_2") (pintype "passive"))
      (node (ref "C87") (pin "2") (pinfunction "2_2") (pintype "passive"))
      (node (ref "C88") (pin "1") (pinfunction "1_1") (pintype "passive"))
      (node (ref "C9") (pin "2") (pinfunction "2_2") (pintype "passive"))
      (node (ref "C91") (pin "-") (pinfunction "-_-") (pintype "passive"))
      (node (ref "C92") (pin "2") (pinfunction "2_2") (pintype "passive"))
      (node (ref "C93") (pin "2") (pinfunction "2_2") (pintype "passive"))
      (node (ref "C94") (pin "2") (pinfunction "2_2") (pintype "passive"))
      (node (ref "C95") (pin "2") (pinfunction "2_2") (pintype "passive"))
      (node (ref "C96") (pin "2") (pinfunction "2_2") (pintype "passive"))
      (node (ref "C97") (pin "2") (pinfunction "2_2") (pintype "passive"))
      (node (ref "C98") (pin "2") (pinfunction "2_2") (pintype "passive"))
      (node (ref "C99") (pin "2") (pinfunction "2_2") (pintype "passive"))
      (node (ref "D3") (pin "1") (pinfunction "1_1") (pintype "bidirectional"))
      (node (ref "ESP1") (pin "9") (pinfunction "GND_9") (pintype "power_in"))
      (node (ref "EXP_1") (pin "9") (pinfunction "S_9") (pintype "passive"))
      (node (ref "EXP_2") (pin "9") (pinfunction "S_9") (pintype "passive"))
      (node (ref "F1") (pin "2") (pinfunction "2_2") (pintype "passive"))
      (node (ref "IC1") (pin "1") (pinfunction "GND_1") (pintype "passive"))
      (node (ref "IC10") (pin "1") (pinfunction "CLK_1") (pintype "bidirectional"))
      (node (ref "IC10") (pin "11") (pinfunction "GND_11") (pintype "power_in"))
      (node (ref "IC10") (pin "12") (pinfunction "GND_12") (pintype "power_in"))
      (node (ref "IC10") (pin "18") (pinfunction "ENCB_DCEN_CFG4_18") (pintype "bidirectional"))
      (node (ref "IC10") (pin "24") (pinfunction "GNDA_24") (pintype "power_in"))
      (node (ref "IC10") (pin "35") (pinfunction "GND_35") (pintype "power_in"))
      (node (ref "IC10") (pin "36") (pinfunction "TST_MODE_36") (pintype "bidirectional"))
      (node (ref "IC10") (pin "TP") (pinfunction "GND_TP") (pintype "power_in"))
      (node (ref "IC11") (pin "7") (pinfunction "GND_7") (pintype "power_in"))
      (node (ref "IC2") (pin "2") (pinfunction "GND-2_2") (pintype "bidirectional"))
      (node (ref "IC2") (pin "26") (pinfunction "GND-26_26") (pintype "bidirectional"))
      (node (ref "IC2") (pin "45") (pinfunction "GND-45_45") (pintype "bidirectional"))
      (node (ref "IC2") (pin "61") (pinfunction "TST_61") (pintype "bidirectional"))
      (node (ref "IC2") (pin "70") (pinfunction "GND-70_70") (pintype "bidirectional"))
      (node (ref "IC2") (pin "77") (pinfunction "JTAGSEL_77") (pintype "bidirectional"))
      (node (ref "IC2") (pin "95") (pinfunction "GND-95_95") (pintype "bidirectional"))
      (node (ref "IC3") (pin "3") (pinfunction "C1_3") (pintype "output"))
      (node (ref "IC3") (pin "5") (pinfunction "GND_5") (pintype "power_in"))
      (node (ref "IC4") (pin "1") (pinfunction "OE_1") (pintype "input"))
      (node (ref "IC4") (pin "12") (pinfunction "I_12") (pintype "input"))
      (node (ref "IC4") (pin "13") (pinfunction "OE_13") (pintype "input"))
      (node (ref "IC4") (pin "4") (pinfunction "OE_4") (pintype "input"))
      (node (ref "IC4") (pin "7") (pinfunction "GND_7") (pintype "power_in"))
      (node (ref "IC5") (pin "10") (pinfunction "I1_10") (pintype "input"))
      (node (ref "IC5") (pin "7") (pinfunction "GND_7") (pintype "power_in"))
      (node (ref "IC5") (pin "9") (pinfunction "I0_9") (pintype "input"))
      (node (ref "IC6") (pin "1") (pinfunction "CLK_1") (pintype "bidirectional"))
      (node (ref "IC6") (pin "11") (pinfunction "GND_11") (pintype "power_in"))
      (node (ref "IC6") (pin "12") (pinfunction "GND_12") (pintype "power_in"))
      (node (ref "IC6") (pin "18") (pinfunction "ENCB_DCEN_CFG4_18") (pintype "bidirectional"))
      (node (ref "IC6") (pin "24") (pinfunction "GNDA_24") (pintype "power_in"))
      (node (ref "IC6") (pin "35") (pinfunction "GND_35") (pintype "power_in"))
      (node (ref "IC6") (pin "36") (pinfunction "TST_MODE_36") (pintype "bidirectional"))
      (node (ref "IC6") (pin "TP") (pinfunction "GND_TP") (pintype "power_in"))
      (node (ref "IC7") (pin "1") (pinfunction "CLK_1") (pintype "bidirectional"))
      (node (ref "IC7") (pin "11") (pinfunction "GND_11") (pintype "power_in"))
      (node (ref "IC7") (pin "12") (pinfunction "GND_12") (pintype "power_in"))
      (node (ref "IC7") (pin "18") (pinfunction "ENCB_DCEN_CFG4_18") (pintype "bidirectional"))
      (node (ref "IC7") (pin "24") (pinfunction "GNDA_24") (pintype "power_in"))
      (node (ref "IC7") (pin "35") (pinfunction "GND_35") (pintype "power_in"))
      (node (ref "IC7") (pin "36") (pinfunction "TST_MODE_36") (pintype "bidirectional"))
      (node (ref "IC7") (pin "TP") (pinfunction "GND_TP") (pintype "power_in"))
      (node (ref "IC8") (pin "1") (pinfunction "CLK_1") (pintype "bidirectional"))
      (node (ref "IC8") (pin "11") (pinfunction "GND_11") (pintype "power_in"))
      (node (ref "IC8") (pin "12") (pinfunction "GND_12") (pintype "power_in"))
      (node (ref "IC8") (pin "18") (pinfunction "ENCB_DCEN_CFG4_18") (pintype "bidirectional"))
      (node (ref "IC8") (pin "24") (pinfunction "GNDA_24") (pintype "power_in"))
      (node (ref "IC8") (pin "35") (pinfunction "GND_35") (pintype "power_in"))
      (node (ref "IC8") (pin "36") (pinfunction "TST_MODE_36") (pintype "bidirectional"))
      (node (ref "IC8") (pin "TP") (pinfunction "GND_TP") (pintype "power_in"))
      (node (ref "IC9") (pin "1") (pinfunction "CLK_1") (pintype "bidirectional"))
      (node (ref "IC9") (pin "11") (pinfunction "GND_11") (pintype "power_in"))
      (node (ref "IC9") (pin "12") (pinfunction "GND_12") (pintype "power_in"))
      (node (ref "IC9") (pin "18") (pinfunction "ENCB_DCEN_CFG4_18") (pintype "bidirectional"))
      (node (ref "IC9") (pin "24") (pinfunction "GNDA_24") (pintype "power_in"))
      (node (ref "IC9") (pin "35") (pinfunction "GND_35") (pintype "power_in"))
      (node (ref "IC9") (pin "36") (pinfunction "TST_MODE_36") (pintype "bidirectional"))
      (node (ref "IC9") (pin "TP") (pinfunction "GND_TP") (pintype "power_in"))
      (node (ref "J1") (pin "G1") (pinfunction "GND_G1") (pintype "power_in"))
      (node (ref "J1") (pin "G2") (pinfunction "GND_G2") (pintype "power_in"))
      (node (ref "J1") (pin "G3") (pinfunction "GND_G3") (pintype "power_in"))
      (node (ref "J1") (pin "G4") (pinfunction "GND_G4") (pintype "power_in"))
      (node (ref "J1") (pin "P6") (pinfunction "VSS_P6") (pintype "power_in"))
      (node (ref "PWRIN") (pin "2") (pinfunction "1_2") (pintype "passive"))
      (node (ref "Q1") (pin "1") (pinfunction "S_1") (pintype "passive"))
      (node (ref "Q1") (pin "4") (pinfunction "S_4") (pintype "passive"))
      (node (ref "Q2") (pin "1") (pinfunction "S_1") (pintype "passive"))
      (node (ref "Q2") (pin "4") (pinfunction "S_4") (pintype "passive"))
      (node (ref "Q3") (pin "1") (pinfunction "S_1") (pintype "passive"))
      (node (ref "Q3") (pin "2") (pinfunction "S_2") (pintype "passive"))
      (node (ref "Q3") (pin "3") (pinfunction "S_3") (pintype "passive"))
      (node (ref "Q4") (pin "1") (pinfunction "S_1") (pintype "passive"))
      (node (ref "Q4") (pin "2") (pinfunction "S_2") (pintype "passive"))
      (node (ref "Q4") (pin "3") (pinfunction "S_3") (pintype "passive"))
      (node (ref "R10") (pin "2") (pinfunction "2_2") (pintype "passive"))
      (node (ref "R11") (pin "2") (pinfunction "2_2") (pintype "passive"))
      (node (ref "R13") (pin "2") (pinfunction "2_2") (pintype "passive"))
      (node (ref "R17") (pin "2") (pinfunction "2_2") (pintype "passive"))
      (node (ref "R2") (pin "1") (pinfunction "1_1") (pintype "passive"))
      (node (ref "R22") (pin "1") (pinfunction "1_1") (pintype "passive"))
      (node (ref "R50") (pin "2") (pinfunction "2_2") (pintype "passive"))
      (node (ref "R51") (pin "2") (pinfunction "2_2") (pintype "passive"))
      (node (ref "R52") (pin "3") (pinfunction "E_3") (pintype "passive"))
      (node (ref "R54") (pin "2") (pinfunction "2_2") (pintype "passive"))
      (node (ref "R55") (pin "2") (pinfunction "2_2") (pintype "passive"))
      (node (ref "R56") (pin "3") (pinfunction "E_3") (pintype "passive"))
      (node (ref "R58") (pin "2") (pinfunction "2_2") (pintype "passive"))
      (node (ref "R59") (pin "2") (pinfunction "2_2") (pintype "passive"))
      (node (ref "R60") (pin "3") (pinfunction "E_3") (pintype "passive"))
      (node (ref "R62") (pin "2") (pinfunction "2_2") (pintype "passive"))
      (node (ref "R63") (pin "2") (pinfunction "2_2") (pintype "passive"))
      (node (ref "R64") (pin "3") (pinfunction "E_3") (pintype "passive"))
      (node (ref "R66") (pin "2") (pinfunction "2_2") (pintype "passive"))
      (node (ref "R67") (pin "2") (pinfunction "2_2") (pintype "passive"))
      (node (ref "R68") (pin "3") (pinfunction "E_3") (pintype "passive"))
      (node (ref "R7") (pin "1") (pinfunction "1_1") (pintype "passive"))
      (node (ref "R8") (pin "2") (pinfunction "2_2") (pintype "passive"))
      (node (ref "R9") (pin "2") (pinfunction "2_2") (pintype "passive"))
      (node (ref "RESET") (pin "B") (pinfunction "S_B") (pintype "passive"))
      (node (ref "RESET") (pin "B'") (pinfunction "S1_B'") (pintype "passive"))
      (node (ref "U1") (pin "10") (pinfunction "DIS_10") (pintype "bidirectional"))
      (node (ref "U1") (pin "13") (pinfunction "NC13_13") (pintype "bidirectional"))
      (node (ref "U1") (pin "14") (pinfunction "NC14_14") (pintype "bidirectional"))
      (node (ref "U1") (pin "15") (pinfunction "NC15_15") (pintype "bidirectional"))
      (node (ref "U1") (pin "16") (pinfunction "NC16_16") (pintype "bidirectional"))
      (node (ref "U1") (pin "2") (pinfunction "NC2_2") (pintype "bidirectional"))
      (node (ref "U1") (pin "6") (pinfunction "GND_6") (pintype "bidirectional"))
      (node (ref "U1") (pin "7") (pinfunction "NC7_7") (pintype "bidirectional"))
      (node (ref "U1") (pin "EXP") (pinfunction "PAD_EXP") (pintype "bidirectional"))
      (node (ref "X1") (pin "4") (pinfunction "4_4") (pintype "bidirectional"))
      (node (ref "X1") (pin "P$1") (pinfunction "P$1_P$1") (pintype "bidirectional"))
      (node (ref "X1") (pin "P$2") (pinfunction "P$2_P$2") (pintype "bidirectional"))
      (node (ref "X2") (pin "2") (pinfunction "2_2") (pintype "passive"))
      (node (ref "X2") (pin "4") (pinfunction "4_4") (pintype "passive"))
      (node (ref "X3") (pin "2") (pinfunction "S_2") (pintype "passive"))
      (node (ref "X_STOP") (pin "3") (pinfunction "S_3") (pintype "passive"))
      (node (ref "Y_STOP") (pin "3") (pinfunction "S_3") (pintype "passive"))
      (node (ref "Z_STOP") (pin "3") (pinfunction "S_3") (pintype "passive"))
    )
    (net (code "83") (name "Net-(3V1-PadC)") (class "Default")
      (node (ref "3V1") (pin "C") (pinfunction "C_C") (pintype "passive"))
      (node (ref "R10") (pin "1") (pinfunction "1_1") (pintype "passive"))
    )
    (net (code "84") (name "Net-(5V-PadC)") (class "Default")
      (node (ref "5V") (pin "C") (pinfunction "C_C") (pintype "passive"))
      (node (ref "R9") (pin "1") (pinfunction "1_1") (pintype "passive"))
    )
    (net (code "85") (name "Net-(BEDA-S)") (class "Default")
      (node (ref "BED") (pin "1") (pinfunction "S_1") (pintype "passive"))
      (node (ref "R36") (pin "2") (pinfunction "2_2") (pintype "passive"))
      (node (ref "R41") (pin "1") (pinfunction "1_1") (pintype "passive"))
    )
    (net (code "86") (name "Net-(C2-Pad1)") (class "Default")
      (node (ref "C2") (pin "1") (pinfunction "1_1") (pintype "passive"))
      (node (ref "C3") (pin "+") (pinfunction "+_+") (pintype "passive"))
      (node (ref "D1") (pin "C") (pinfunction "C_C") (pintype "passive"))
      (node (ref "L1") (pin "1") (pinfunction "1_1") (pintype "passive"))
    )
    (net (code "87") (name "Net-(C26-Pad1)") (class "Default")
      (node (ref "C26") (pin "1") (pinfunction "1_1") (pintype "passive"))
      (node (ref "R15") (pin "1") (pinfunction "1_1") (pintype "passive"))
    )
    (net (code "88") (name "Net-(D2-A)") (class "Default")
      (node (ref "D2") (pin "P$2") (pinfunction "A_P$2") (pintype "bidirectional"))
      (node (ref "R4") (pin "2") (pinfunction "2_2") (pintype "passive"))
      (node (ref "R5") (pin "2") (pinfunction "2_2") (pintype "passive"))
      (node (ref "U1") (pin "8") (pinfunction "ISEN_8") (pintype "bidirectional"))
    )
    (net (code "89") (name "Net-(D2-K)") (class "Default")
      (node (ref "C7") (pin "2") (pinfunction "2_2") (pintype "passive"))
      (node (ref "D2") (pin "P$1") (pinfunction "K_P$1") (pintype "bidirectional"))
      (node (ref "L2") (pin "P$1") (pinfunction "1_P$1") (pintype "passive"))
      (node (ref "U1") (pin "12") (pinfunction "LX_12") (pintype "bidirectional"))
    )
    (net (code "90") (name "Net-(ESP1-GPIO0)") (class "Default")
      (node (ref "ESP1") (pin "12") (pinfunction "GPIO0_12") (pintype "bidirectional"))
      (node (ref "R25") (pin "2") (pinfunction "2_2") (pintype "passive"))
    )
    (net (code "91") (name "Net-(ESP1-GPIO12)") (class "Default")
      (node (ref "ESP1") (pin "6") (pinfunction "GPIO12_6") (pintype "bidirectional"))
      (node (ref "R20") (pin "1") (pinfunction "1_1") (pintype "passive"))
    )
    (net (code "92") (name "Net-(ESP1-GPIO13)") (class "Default")
      (node (ref "ESP1") (pin "7") (pinfunction "GPIO13_7") (pintype "bidirectional"))
      (node (ref "R21") (pin "1") (pinfunction "1_1") (pintype "passive"))
    )
    (net (code "93") (name "Net-(ESP1-GPIO14)") (class "Default")
      (node (ref "ESP1") (pin "5") (pinfunction "GPIO14_5") (pintype "bidirectional"))
      (node (ref "R19") (pin "1") (pinfunction "1_1") (pintype "passive"))
    )
    (net (code "94") (name "Net-(ESP1-GPIO15)") (class "Default")
      (node (ref "ESP1") (pin "10") (pinfunction "GPIO15_10") (pintype "bidirectional"))
      (node (ref "R26") (pin "2") (pinfunction "2_2") (pintype "passive"))
    )
    (net (code "95") (name "Net-(ESP1-RESET)") (class "Default")
      (node (ref "ESP1") (pin "1") (pinfunction "RESET_1") (pintype "input"))
      (node (ref "R18") (pin "2") (pinfunction "2_2") (pintype "passive"))
      (node (ref "R22") (pin "2") (pinfunction "2_2") (pintype "passive"))
    )
    (net (code "96") (name "Net-(ESP1-RXD)") (class "Default")
      (node (ref "ESP1") (pin "15") (pinfunction "RXD_15") (pintype "input"))
      (node (ref "R24") (pin "2") (pinfunction "2_2") (pintype "passive"))
    )
    (net (code "97") (name "Net-(ESP1-TXD)") (class "Default")
      (node (ref "ESP1") (pin "16") (pinfunction "TXD_16") (pintype "output"))
      (node (ref "R23") (pin "2") (pinfunction "2_2") (pintype "passive"))
    )
    (net (code "98") (name "Net-(ESP1-VCC)") (class "Default")
      (node (ref "ESP1") (pin "8") (pinfunction "VCC_8") (pintype "power_in"))
      (node (ref "L6") (pin "2") (pinfunction "2_2") (pintype "passive"))
    )
    (net (code "99") (name "Net-(EXP_1C-S)") (class "Default")
      (node (ref "EXP_1") (pin "2") (pinfunction "S_2") (pintype "passive"))
      (node (ref "IC4") (pin "6") (pinfunction "O_6") (pintype "tri_state"))
    )
    (net (code "100") (name "Net-(EXP_1G-S)") (class "Default")
      (node (ref "EXP_1") (pin "6") (pinfunction "S_6") (pintype "passive"))
      (node (ref "IC4") (pin "3") (pinfunction "O_3") (pintype "tri_state"))
    )
    (net (code "101") (name "Net-(EXP_2E-S)") (class "Default")
      (node (ref "EXP_2") (pin "4") (pinfunction "S_4") (pintype "passive"))
      (node (ref "IC5") (pin "6") (pinfunction "O_6") (pintype "output"))
    )
    (net (code "102") (name "Net-(EXT1A-S)") (class "Default")
      (node (ref "EXT1") (pin "1") (pinfunction "S_1") (pintype "passive"))
      (node (ref "R37") (pin "2") (pinfunction "2_2") (pintype "passive"))
      (node (ref "R40") (pin "1") (pinfunction "1_1") (pintype "passive"))
    )
    (net (code "103") (name "Net-(EXT1_L-PadA)") (class "Default")
      (node (ref "EXT1_L") (pin "A") (pinfunction "A_A") (pintype "passive"))
      (node (ref "R48") (pin "1") (pinfunction "1_1") (pintype "passive"))
    )
    (net (code "104") (name "Net-(EXT1_L-PadC)") (class "Default")
      (node (ref "EXT1_L") (pin "C") (pinfunction "C_C") (pintype "passive"))
      (node (ref "J2") (pin "1") (pinfunction "1_1") (pintype "passive"))
      (node (ref "Q3") (pin "EXP") (pinfunction "D_EXP") (pintype "passive"))
      (node (ref "Q3") (pin "MB") (pinfunction "D_MB") (pintype "passive"))
    )
    (net (code "105") (name "Net-(EXT2A-S)") (class "Default")
      (node (ref "EXT2") (pin "1") (pinfunction "S_1") (pintype "passive"))
      (node (ref "R38") (pin "2") (pinfunction "2_2") (pintype "passive"))
      (node (ref "R39") (pin "1") (pinfunction "1_1") (pintype "passive"))
    )
    (net (code "106") (name "Net-(EXT2_L-PadA)") (class "Default")
      (node (ref "EXT2_L") (pin "A") (pinfunction "A_A") (pintype "passive"))
      (node (ref "R49") (pin "1") (pinfunction "1_1") (pintype "passive"))
    )
    (net (code "107") (name "Net-(FAN1B-S)") (class "Default")
      (node (ref "FAN1") (pin "2") (pinfunction "S_2") (pintype "passive"))
      (node (ref "Q1") (pin "6") (pinfunction "D_6") (pintype "passive"))
    )
    (net (code "108") (name "Net-(FAN2B-S)") (class "Default")
      (node (ref "FAN2") (pin "2") (pinfunction "S_2") (pintype "passive"))
      (node (ref "Q1") (pin "3") (pinfunction "D_3") (pintype "passive"))
    )
    (net (code "109") (name "Net-(FAN3B-S)") (class "Default")
      (node (ref "FAN3") (pin "2") (pinfunction "S_2") (pintype "passive"))
      (node (ref "Q2") (pin "6") (pinfunction "D_6") (pintype "passive"))
    )
    (net (code "110") (name "Net-(FAN4B-S)") (class "Default")
      (node (ref "FAN4") (pin "2") (pinfunction "S_2") (pintype "passive"))
      (node (ref "Q2") (pin "3") (pinfunction "D_3") (pintype "passive"))
    )
    (net (code "111") (name "Net-(IC2-ERASE{slash}PB12)") (class "Default")
      (node (ref "ERASE") (pin "2") (pinfunction "2_2") (pintype "passive"))
      (node (ref "IC2") (pin "87") (pinfunction "ERASE/PB12_87") (pintype "bidirectional"))
    )
    (net (code "112") (name "Net-(IC2-PB8{slash}XOUT)") (class "Default")
      (node (ref "C37") (pin "1") (pinfunction "1_1") (pintype "passive"))
      (node (ref "IC2") (pin "96") (pinfunction "PB8/XOUT_96") (pintype "bidirectional"))
      (node (ref "X2") (pin "1") (pinfunction "1_1") (pintype "passive"))
    )
    (net (code "113") (name "Net-(IC2-PB9{slash}PGMCK{slash}XIN)") (class "Default")
      (node (ref "C36") (pin "1") (pinfunction "1_1") (pintype "passive"))
      (node (ref "IC2") (pin "97") (pinfunction "PB9/PGMCK/XIN_97") (pintype "bidirectional"))
      (node (ref "X2") (pin "3") (pinfunction "3_3") (pintype "passive"))
    )
    (net (code "114") (name "Net-(IC2-VDDCORE-16)") (class "Default")
      (node (ref "C28") (pin "1") (pinfunction "1_1") (pintype "passive"))
      (node (ref "C29") (pin "1") (pinfunction "1_1") (pintype "passive"))
      (node (ref "C30") (pin "1") (pinfunction "1_1") (pintype "passive"))
      (node (ref "C31") (pin "1") (pinfunction "1_1") (pintype "passive"))
      (node (ref "C32") (pin "1") (pinfunction "1_1") (pintype "passive"))
      (node (ref "C33") (pin "1") (pinfunction "1_1") (pintype "passive"))
      (node (ref "C34") (pin "1") (pinfunction "1_1") (pintype "passive"))
      (node (ref "IC2") (pin "11") (pinfunction "VDDOUT_11") (pintype "bidirectional"))
      (node (ref "IC2") (pin "16") (pinfunction "VDDCORE-16_16") (pintype "bidirectional"))
      (node (ref "IC2") (pin "36") (pinfunction "VDDCORE-36_36") (pintype "bidirectional"))
      (node (ref "IC2") (pin "56") (pinfunction "VDDCORE-56_56") (pintype "bidirectional"))
      (node (ref "IC2") (pin "85") (pinfunction "VDDCORE-85_85") (pintype "bidirectional"))
      (node (ref "L5") (pin "2") (pinfunction "2_2") (pintype "passive"))
    )
    (net (code "115") (name "Net-(IC2-VDDPLL)") (class "Default")
      (node (ref "C27") (pin "1") (pinfunction "1_1") (pintype "passive"))
      (node (ref "IC2") (pin "100") (pinfunction "VDDPLL_100") (pintype "bidirectional"))
      (node (ref "L5") (pin "1") (pinfunction "1_1") (pintype "passive"))
      (node (ref "R15") (pin "2") (pinfunction "2_2") (pintype "passive"))
    )
    (net (code "116") (name "Net-(IC6-5VOUT)") (class "Default")
      (node (ref "C48") (pin "1") (pinfunction "1_1") (pintype "passive"))
      (node (ref "IC6") (pin "25") (pinfunction "5VOUT_25") (pintype "power_in"))
    )
    (net (code "117") (name "Net-(IC6-AIN_IREF)") (class "Default")
      (node (ref "IC6") (pin "23") (pinfunction "AIN_IREF_23") (pintype "passive"))
      (node (ref "R52") (pin "2") (pinfunction "S_2") (pintype "passive"))
    )
    (net (code "118") (name "Net-(IC6-BRA)") (class "Default")
      (node (ref "IC6") (pin "33") (pinfunction "BRA_33") (pintype "output"))
      (node (ref "R50") (pin "1") (pinfunction "1_1") (pintype "passive"))
    )
    (net (code "119") (name "Net-(IC6-BRB)") (class "Default")
      (node (ref "IC6") (pin "14") (pinfunction "BRB_14") (pintype "output"))
      (node (ref "R51") (pin "1") (pinfunction "1_1") (pintype "passive"))
    )
    (net (code "120") (name "Net-(IC6-CPI)") (class "Default")
      (node (ref "C51") (pin "1") (pinfunction "1_1") (pintype "passive"))
      (node (ref "IC6") (pin "28") (pinfunction "CPI_28") (pintype "passive"))
    )
    (net (code "121") (name "Net-(IC6-CPO)") (class "Default")
      (node (ref "C51") (pin "2") (pinfunction "2_2") (pintype "passive"))
      (node (ref "IC6") (pin "27") (pinfunction "CPO_27") (pintype "passive"))
    )
    (net (code "122") (name "Net-(IC6-OA1)") (class "Default")
      (node (ref "C55") (pin "1") (pinfunction "1_1") (pintype "passive"))
      (node (ref "IC6") (pin "34") (pinfunction "OA1_34") (pintype "output"))
      (node (ref "X4") (pin "1") (pinfunction "S_1") (pintype "passive"))
    )
    (net (code "123") (name "Net-(IC6-OA2)") (class "Default")
      (node (ref "C56") (pin "1") (pinfunction "1_1") (pintype "passive"))
      (node (ref "IC6") (pin "32") (pinfunction "OA2_32") (pintype "output"))
      (node (ref "X4") (pin "2") (pinfunction "S_2") (pintype "passive"))
    )
    (net (code "124") (name "Net-(IC6-OB1)") (class "Default")
      (node (ref "C57") (pin "1") (pinfunction "1_1") (pintype "passive"))
      (node (ref "IC6") (pin "13") (pinfunction "OB1_13") (pintype "output"))
      (node (ref "X4") (pin "3") (pinfunction "S_3") (pintype "passive"))
    )
    (net (code "125") (name "Net-(IC6-OB2)") (class "Default")
      (node (ref "C58") (pin "1") (pinfunction "1_1") (pintype "passive"))
      (node (ref "IC6") (pin "15") (pinfunction "OB2_15") (pintype "output"))
      (node (ref "X4") (pin "4") (pinfunction "S_4") (pintype "passive"))
    )
    (net (code "126") (name "Net-(IC6-VCP)") (class "Default")
      (node (ref "C50") (pin "2") (pinfunction "2_2") (pintype "passive"))
      (node (ref "IC6") (pin "29") (pinfunction "VCP_29") (pintype "passive"))
    )
    (net (code "127") (name "Net-(IC7-5VOUT)") (class "Default")
      (node (ref "C61") (pin "1") (pinfunction "1_1") (pintype "passive"))
      (node (ref "IC7") (pin "25") (pinfunction "5VOUT_25") (pintype "power_in"))
    )
    (net (code "128") (name "Net-(IC7-AIN_IREF)") (class "Default")
      (node (ref "IC7") (pin "23") (pinfunction "AIN_IREF_23") (pintype "passive"))
      (node (ref "R56") (pin "2") (pinfunction "S_2") (pintype "passive"))
    )
    (net (code "129") (name "Net-(IC7-BRA)") (class "Default")
      (node (ref "IC7") (pin "33") (pinfunction "BRA_33") (pintype "output"))
      (node (ref "R54") (pin "1") (pinfunction "1_1") (pintype "passive"))
    )
    (net (code "130") (name "Net-(IC7-BRB)") (class "Default")
      (node (ref "IC7") (pin "14") (pinfunction "BRB_14") (pintype "output"))
      (node (ref "R55") (pin "1") (pinfunction "1_1") (pintype "passive"))
    )
    (net (code "131") (name "Net-(IC7-CPI)") (class "Default")
      (node (ref "C64") (pin "1") (pinfunction "1_1") (pintype "passive"))
      (node (ref "IC7") (pin "28") (pinfunction "CPI_28") (pintype "passive"))
    )
    (net (code "132") (name "Net-(IC7-CPO)") (class "Default")
      (node (ref "C64") (pin "2") (pinfunction "2_2") (pintype "passive"))
      (node (ref "IC7") (pin "27") (pinfunction "CPO_27") (pintype "passive"))
    )
    (net (code "133") (name "Net-(IC7-OA1)") (class "Default")
      (node (ref "C68") (pin "1") (pinfunction "1_1") (pintype "passive"))
      (node (ref "IC7") (pin "34") (pinfunction "OA1_34") (pintype "output"))
      (node (ref "X5") (pin "1") (pinfunction "S_1") (pintype "passive"))
    )
    (net (code "134") (name "Net-(IC7-OA2)") (class "Default")
      (node (ref "C69") (pin "1") (pinfunction "1_1") (pintype "passive"))
      (node (ref "IC7") (pin "32") (pinfunction "OA2_32") (pintype "output"))
      (node (ref "X5") (pin "2") (pinfunction "S_2") (pintype "passive"))
    )
    (net (code "135") (name "Net-(IC7-OB1)") (class "Default")
      (node (ref "C70") (pin "1") (pinfunction "1_1") (pintype "passive"))
      (node (ref "IC7") (pin "13") (pinfunction "OB1_13") (pintype "output"))
      (node (ref "X5") (pin "3") (pinfunction "S_3") (pintype "passive"))
    )
    (net (code "136") (name "Net-(IC7-OB2)") (class "Default")
      (node (ref "C71") (pin "1") (pinfunction "1_1") (pintype "passive"))
      (node (ref "IC7") (pin "15") (pinfunction "OB2_15") (pintype "output"))
      (node (ref "X5") (pin "4") (pinfunction "S_4") (pintype "passive"))
    )
    (net (code "137") (name "Net-(IC7-VCP)") (class "Default")
      (node (ref "C63") (pin "2") (pinfunction "2_2") (pintype "passive"))
      (node (ref "IC7") (pin "29") (pinfunction "VCP_29") (pintype "passive"))
    )
    (net (code "138") (name "Net-(IC8-5VOUT)") (class "Default")
      (node (ref "C74") (pin "1") (pinfunction "1_1") (pintype "passive"))
      (node (ref "IC8") (pin "25") (pinfunction "5VOUT_25") (pintype "power_in"))
    )
    (net (code "139") (name "Net-(IC8-AIN_IREF)") (class "Default")
      (node (ref "IC8") (pin "23") (pinfunction "AIN_IREF_23") (pintype "passive"))
      (node (ref "R60") (pin "2") (pinfunction "S_2") (pintype "passive"))
    )
    (net (code "140") (name "Net-(IC8-BRA)") (class "Default")
      (node (ref "IC8") (pin "33") (pinfunction "BRA_33") (pintype "output"))
      (node (ref "R58") (pin "1") (pinfunction "1_1") (pintype "passive"))
    )
    (net (code "141") (name "Net-(IC8-BRB)") (class "Default")
      (node (ref "IC8") (pin "14") (pinfunction "BRB_14") (pintype "output"))
      (node (ref "R59") (pin "1") (pinfunction "1_1") (pintype "passive"))
    )
    (net (code "142") (name "Net-(IC8-CPI)") (class "Default")
      (node (ref "C77") (pin "1") (pinfunction "1_1") (pintype "passive"))
      (node (ref "IC8") (pin "28") (pinfunction "CPI_28") (pintype "passive"))
    )
    (net (code "143") (name "Net-(IC8-CPO)") (class "Default")
      (node (ref "C77") (pin "2") (pinfunction "2_2") (pintype "passive"))
      (node (ref "IC8") (pin "27") (pinfunction "CPO_27") (pintype "passive"))
    )
    (net (code "144") (name "Net-(IC8-OA1)") (class "Default")
      (node (ref "C81") (pin "1") (pinfunction "1_1") (pintype "passive"))
      (node (ref "IC8") (pin "34") (pinfunction "OA1_34") (pintype "output"))
      (node (ref "X9") (pin "1") (pinfunction "S_1") (pintype "passive"))
    )
    (net (code "145") (name "Net-(IC8-OA2)") (class "Default")
      (node (ref "C82") (pin "1") (pinfunction "1_1") (pintype "passive"))
      (node (ref "IC8") (pin "32") (pinfunction "OA2_32") (pintype "output"))
      (node (ref "X6") (pin "2") (pinfunction "S_2") (pintype "passive"))
    )
    (net (code "146") (name "Net-(IC8-OB1)") (class "Default")
      (node (ref "C83") (pin "1") (pinfunction "1_1") (pintype "passive"))
      (node (ref "IC8") (pin "13") (pinfunction "OB1_13") (pintype "output"))
      (node (ref "X6") (pin "3") (pinfunction "S_3") (pintype "passive"))
    )
    (net (code "147") (name "Net-(IC8-OB2)") (class "Default")
      (node (ref "C84") (pin "1") (pinfunction "1_1") (pintype "passive"))
      (node (ref "IC8") (pin "15") (pinfunction "OB2_15") (pintype "output"))
      (node (ref "X9") (pin "4") (pinfunction "S_4") (pintype "passive"))
    )
    (net (code "148") (name "Net-(IC8-VCP)") (class "Default")
      (node (ref "C76") (pin "2") (pinfunction "2_2") (pintype "passive"))
      (node (ref "IC8") (pin "29") (pinfunction "VCP_29") (pintype "passive"))
    )
    (net (code "149") (name "Net-(IC9-5VOUT)") (class "Default")
      (node (ref "C87") (pin "1") (pinfunction "1_1") (pintype "passive"))
      (node (ref "IC9") (pin "25") (pinfunction "5VOUT_25") (pintype "power_in"))
    )
    (net (code "150") (name "Net-(IC9-AIN_IREF)") (class "Default")
      (node (ref "IC9") (pin "23") (pinfunction "AIN_IREF_23") (pintype "passive"))
      (node (ref "R64") (pin "2") (pinfunction "S_2") (pintype "passive"))
    )
    (net (code "151") (name "Net-(IC9-BRA)") (class "Default")
      (node (ref "IC9") (pin "33") (pinfunction "BRA_33") (pintype "output"))
      (node (ref "R62") (pin "1") (pinfunction "1_1") (pintype "passive"))
    )
    (net (code "152") (name "Net-(IC9-BRB)") (class "Default")
      (node (ref "IC9") (pin "14") (pinfunction "BRB_14") (pintype "output"))
      (node (ref "R63") (pin "1") (pinfunction "1_1") (pintype "passive"))
    )
    (net (code "153") (name "Net-(IC9-CPI)") (class "Default")
      (node (ref "C90") (pin "1") (pinfunction "1_1") (pintype "passive"))
      (node (ref "IC9") (pin "28") (pinfunction "CPI_28") (pintype "passive"))
    )
    (net (code "154") (name "Net-(IC9-CPO)") (class "Default")
      (node (ref "C90") (pin "2") (pinfunction "2_2") (pintype "passive"))
      (node (ref "IC9") (pin "27") (pinfunction "CPO_27") (pintype "passive"))
    )
    (net (code "155") (name "Net-(IC9-OA1)") (class "Default")
      (node (ref "C94") (pin "1") (pinfunction "1_1") (pintype "passive"))
      (node (ref "IC9") (pin "34") (pinfunction "OA1_34") (pintype "output"))
      (node (ref "X7") (pin "1") (pinfunction "S_1") (pintype "passive"))
    )
    (net (code "156") (name "Net-(IC9-OA2)") (class "Default")
      (node (ref "C95") (pin "1") (pinfunction "1_1") (pintype "passive"))
      (node (ref "IC9") (pin "32") (pinfunction "OA2_32") (pintype "output"))
      (node (ref "X7") (pin "2") (pinfunction "S_2") (pintype "passive"))
    )
    (net (code "157") (name "Net-(IC9-OB1)") (class "Default")
      (node (ref "C96") (pin "1") (pinfunction "1_1") (pintype "passive"))
      (node (ref "IC9") (pin "13") (pinfunction "OB1_13") (pintype "output"))
      (node (ref "X7") (pin "3") (pinfunction "S_3") (pintype "passive"))
    )
    (net (code "158") (name "Net-(IC9-OB2)") (class "Default")
      (node (ref "C97") (pin "1") (pinfunction "1_1") (pintype "passive"))
      (node (ref "IC9") (pin "15") (pinfunction "OB2_15") (pintype "output"))
      (node (ref "X7") (pin "4") (pinfunction "S_4") (pintype "passive"))
    )
    (net (code "159") (name "Net-(IC9-VCP)") (class "Default")
      (node (ref "C89") (pin "2") (pinfunction "2_2") (pintype "passive"))
      (node (ref "IC9") (pin "29") (pinfunction "VCP_29") (pintype "passive"))
    )
    (net (code "160") (name "Net-(IC10-5VOUT)") (class "Default")
      (node (ref "C100") (pin "1") (pinfunction "1_1") (pintype "passive"))
      (node (ref "IC10") (pin "25") (pinfunction "5VOUT_25") (pintype "power_in"))
    )
    (net (code "161") (name "Net-(IC10-AIN_IREF)") (class "Default")
      (node (ref "IC10") (pin "23") (pinfunction "AIN_IREF_23") (pintype "passive"))
      (node (ref "R68") (pin "2") (pinfunction "S_2") (pintype "passive"))
    )
    (net (code "162") (name "Net-(IC10-BRA)") (class "Default")
      (node (ref "IC10") (pin "33") (pinfunction "BRA_33") (pintype "output"))
      (node (ref "R66") (pin "1") (pinfunction "1_1") (pintype "passive"))
    )
    (net (code "163") (name "Net-(IC10-BRB)") (class "Default")
      (node (ref "IC10") (pin "14") (pinfunction "BRB_14") (pintype "output"))
      (node (ref "R67") (pin "1") (pinfunction "1_1") (pintype "passive"))
    )
    (net (code "164") (name "Net-(IC10-CPI)") (class "Default")
      (node (ref "C103") (pin "1") (pinfunction "1_1") (pintype "passive"))
      (node (ref "IC10") (pin "28") (pinfunction "CPI_28") (pintype "passive"))
    )
    (net (code "165") (name "Net-(IC10-CPO)") (class "Default")
      (node (ref "C103") (pin "2") (pinfunction "2_2") (pintype "passive"))
      (node (ref "IC10") (pin "27") (pinfunction "CPO_27") (pintype "passive"))
    )
    (net (code "166") (name "Net-(IC10-OA1)") (class "Default")
      (node (ref "C107") (pin "1") (pinfunction "1_1") (pintype "passive"))
      (node (ref "IC10") (pin "34") (pinfunction "OA1_34") (pintype "output"))
      (node (ref "X8") (pin "1") (pinfunction "S_1") (pintype "passive"))
    )
    (net (code "167") (name "Net-(IC10-OA2)") (class "Default")
      (node (ref "C108") (pin "1") (pinfunction "1_1") (pintype "passive"))
      (node (ref "IC10") (pin "32") (pinfunction "OA2_32") (pintype "output"))
      (node (ref "X8") (pin "2") (pinfunction "S_2") (pintype "passive"))
    )
    (net (code "168") (name "Net-(IC10-OB1)") (class "Default")
      (node (ref "C109") (pin "1") (pinfunction "1_1") (pintype "passive"))
      (node (ref "IC10") (pin "13") (pinfunction "OB1_13") (pintype "output"))
      (node (ref "X8") (pin "3") (pinfunction "S_3") (pintype "passive"))
    )
    (net (code "169") (name "Net-(IC10-OB2)") (class "Default")
      (node (ref "C110") (pin "1") (pinfunction "1_1") (pintype "passive"))
      (node (ref "IC10") (pin "15") (pinfunction "OB2_15") (pintype "output"))
      (node (ref "X8") (pin "4") (pinfunction "S_4") (pintype "passive"))
    )
    (net (code "170") (name "Net-(IC10-VCP)") (class "Default")
      (node (ref "C102") (pin "2") (pinfunction "2_2") (pintype "passive"))
      (node (ref "IC10") (pin "29") (pinfunction "VCP_29") (pintype "passive"))
    )
    (net (code "171") (name "Net-(IC11A-O)") (class "Default")
      (node (ref "IC11") (pin "12") (pinfunction "I0_12") (pintype "input"))
      (node (ref "IC11") (pin "3") (pinfunction "O_3") (pintype "output"))
    )
    (net (code "172") (name "Net-(IC11B-O)") (class "Default")
      (node (ref "IC11") (pin "10") (pinfunction "I1_10") (pintype "input"))
      (node (ref "IC11") (pin "6") (pinfunction "O_6") (pintype "output"))
    )
    (net (code "173") (name "Net-(IC11C-O)") (class "Default")
      (node (ref "IC11") (pin "13") (pinfunction "I1_13") (pintype "input"))
      (node (ref "IC11") (pin "8") (pinfunction "O_8") (pintype "output"))
    )
    (net (code "174") (name "Net-(J1-CARD_DETECT)") (class "Default")
      (node (ref "J1") (pin "P9") (pinfunction "CARD_DETECT_P9") (pintype "passive"))
      (node (ref "R27") (pin "2") (pinfunction "2_2") (pintype "passive"))
      (node (ref "R34") (pin "1") (pinfunction "1_1") (pintype "passive"))
    )
    (net (code "175") (name "Net-(J1-CLK)") (class "Default")
      (node (ref "J1") (pin "P5") (pinfunction "CLK_P5") (pintype "input"))
      (node (ref "R30") (pin "2") (pinfunction "2_2") (pintype "passive"))
    )
    (net (code "176") (name "Net-(J1-CMD)") (class "Default")
      (node (ref "J1") (pin "P3") (pinfunction "CMD_P3") (pintype "input"))
      (node (ref "R29") (pin "2") (pinfunction "2_2") (pintype "passive"))
      (node (ref "R35") (pin "1") (pinfunction "1_1") (pintype "passive"))
    )
    (net (code "177") (name "Net-(J1-DAT0)") (class "Default")
      (node (ref "J1") (pin "P7") (pinfunction "DAT0_P7") (pintype "output"))
      (node (ref "R28") (pin "2") (pinfunction "2_2") (pintype "passive"))
    )
    (net (code "178") (name "Net-(J1-DAT1)") (class "Default")
      (node (ref "J1") (pin "P8") (pinfunction "DAT1_P8") (pintype "bidirectional"))
      (node (ref "R32") (pin "2") (pinfunction "2_2") (pintype "passive"))
    )
    (net (code "179") (name "Net-(J1-DAT2)") (class "Default")
      (node (ref "J1") (pin "P1") (pinfunction "DAT2_P1") (pintype "bidirectional"))
      (node (ref "R33") (pin "2") (pinfunction "2_2") (pintype "passive"))
    )
    (net (code "180") (name "Net-(J1-DAT3)") (class "Default")
      (node (ref "J1") (pin "P2") (pinfunction "DAT3_P2") (pintype "input"))
      (node (ref "R31") (pin "2") (pinfunction "2_2") (pintype "passive"))
    )
    (net (code "181") (name "Net-(J2B-1)") (class "Default")
      (node (ref "F2") (pin "2") (pinfunction "2_2") (pintype "passive"))
      (node (ref "J2") (pin "2") (pinfunction "1_2") (pintype "passive"))
    )
    (net (code "182") (name "Net-(J2C-1)") (class "Default")
      (node (ref "EXT2_L") (pin "C") (pinfunction "C_C") (pintype "passive"))
      (node (ref "J2") (pin "3") (pinfunction "1_3") (pintype "passive"))
      (node (ref "Q4") (pin "EXP") (pinfunction "D_EXP") (pintype "passive"))
      (node (ref "Q4") (pin "MB") (pinfunction "D_MB") (pintype "passive"))
    )
    (net (code "183") (name "Net-(J2D-1)") (class "Default")
      (node (ref "F3") (pin "2") (pinfunction "2_2") (pintype "passive"))
      (node (ref "J2") (pin "4") (pinfunction "1_4") (pintype "passive"))
    )
    (net (code "184") (name "Net-(L2-2)") (class "Default")
      (node (ref "C10") (pin "1") (pinfunction "1_1") (pintype "passive"))
      (node (ref "C8") (pin "1") (pinfunction "1_1") (pintype "passive"))
      (node (ref "C9") (pin "1") (pinfunction "1_1") (pintype "passive"))
      (node (ref "L2") (pin "P$2") (pinfunction "2_P$2") (pintype "passive"))
      (node (ref "L3") (pin "1") (pinfunction "1_1") (pintype "passive"))
      (node (ref "R6") (pin "2") (pinfunction "2_2") (pintype "passive"))
    )
    (net (code "185") (name "Net-(Q1A-G)") (class "Default")
      (node (ref "Q1") (pin "2") (pinfunction "G_2") (pintype "passive"))
      (node (ref "R42") (pin "2") (pinfunction "2_2") (pintype "passive"))
    )
    (net (code "186") (name "Net-(Q1B-G)") (class "Default")
      (node (ref "Q1") (pin "5") (pinfunction "G_5") (pintype "passive"))
      (node (ref "R43") (pin "2") (pinfunction "2_2") (pintype "passive"))
    )
    (net (code "187") (name "Net-(Q2A-G)") (class "Default")
      (node (ref "Q2") (pin "2") (pinfunction "G_2") (pintype "passive"))
      (node (ref "R44") (pin "2") (pinfunction "2_2") (pintype "passive"))
    )
    (net (code "188") (name "Net-(Q2B-G)") (class "Default")
      (node (ref "Q2") (pin "5") (pinfunction "G_5") (pintype "passive"))
      (node (ref "R45") (pin "2") (pinfunction "2_2") (pintype "passive"))
    )
    (net (code "189") (name "Net-(Q3-G)") (class "Default")
      (node (ref "Q3") (pin "4") (pinfunction "G_4") (pintype "passive"))
      (node (ref "R46") (pin "2") (pinfunction "2_2") (pintype "passive"))
    )
    (net (code "190") (name "Net-(Q4-G)") (class "Default")
      (node (ref "Q4") (pin "4") (pinfunction "G_4") (pintype "passive"))
      (node (ref "R47") (pin "2") (pinfunction "2_2") (pintype "passive"))
    )
    (net (code "191") (name "Net-(R8-Pad1)") (class "Default")
      (node (ref "R8") (pin "1") (pinfunction "1_1") (pintype "passive"))
      (node (ref "VIN") (pin "C") (pinfunction "C_C") (pintype "passive"))
    )
    (net (code "192") (name "Net-(R11-Pad1)") (class "Default")
      (node (ref "R11") (pin "1") (pinfunction "1_1") (pintype "passive"))
      (node (ref "USB") (pin "C") (pinfunction "C_C") (pintype "passive"))
    )
    (net (code "193") (name "Net-(R52-A)") (class "Default")
      (node (ref "R52") (pin "1") (pinfunction "A_1") (pintype "passive"))
      (node (ref "R53") (pin "1") (pinfunction "1_1") (pintype "passive"))
    )
    (net (code "194") (name "Net-(R56-A)") (class "Default")
      (node (ref "R56") (pin "1") (pinfunction "A_1") (pintype "passive"))
      (node (ref "R57") (pin "1") (pinfunction "1_1") (pintype "passive"))
    )
    (net (code "195") (name "Net-(R60-A)") (class "Default")
      (node (ref "R60") (pin "1") (pinfunction "A_1") (pintype "passive"))
      (node (ref "R61") (pin "1") (pinfunction "1_1") (pintype "passive"))
    )
    (net (code "196") (name "Net-(R64-A)") (class "Default")
      (node (ref "R64") (pin "1") (pinfunction "A_1") (pintype "passive"))
      (node (ref "R65") (pin "1") (pinfunction "1_1") (pintype "passive"))
    )
    (net (code "197") (name "Net-(R68-A)") (class "Default")
      (node (ref "R68") (pin "1") (pinfunction "A_1") (pintype "passive"))
      (node (ref "R69") (pin "1") (pinfunction "1_1") (pintype "passive"))
    )
    (net (code "198") (name "Net-(U1-BOOT)") (class "Default")
      (node (ref "C7") (pin "1") (pinfunction "1_1") (pintype "passive"))
      (node (ref "U1") (pin "11") (pinfunction "BOOT_11") (pintype "bidirectional"))
    )
    (net (code "199") (name "Net-(U1-FB)") (class "Default")
      (node (ref "C10") (pin "2") (pinfunction "2_2") (pintype "passive"))
      (node (ref "R6") (pin "1") (pinfunction "1_1") (pintype "passive"))
      (node (ref "R7") (pin "2") (pinfunction "2_2") (pintype "passive"))
      (node (ref "U1") (pin "5") (pinfunction "FB_5") (pintype "bidirectional"))
    )
    (net (code "200") (name "Net-(U1-SGND)") (class "Default")
      (node (ref "R4") (pin "1") (pinfunction "1_1") (pintype "passive"))
      (node (ref "R5") (pin "1") (pinfunction "1_1") (pintype "passive"))
      (node (ref "U1") (pin "9") (pinfunction "SGND_9") (pintype "bidirectional"))
    )
    (net (code "201") (name "Net-(U1-SS)") (class "Default")
      (node (ref "C6") (pin "1") (pinfunction "1_1") (pintype "passive"))
      (node (ref "U1") (pin "4") (pinfunction "SS_4") (pintype "bidirectional"))
    )
    (net (code "202") (name "Net-(U1-TON)") (class "Default")
      (node (ref "R3") (pin "1") (pinfunction "1_1") (pintype "passive"))
      (node (ref "U1") (pin "3") (pinfunction "TON_3") (pintype "bidirectional"))
    )
    (net (code "203") (name "Net-(U1-VIN)") (class "Default")
      (node (ref "C4") (pin "1") (pinfunction "1_1") (pintype "passive"))
      (node (ref "C5") (pin "+") (pinfunction "+_+") (pintype "passive"))
      (node (ref "L1") (pin "2") (pinfunction "2_2") (pintype "passive"))
      (node (ref "R3") (pin "2") (pinfunction "2_2") (pintype "passive"))
      (node (ref "U1") (pin "1") (pinfunction "VIN_1") (pintype "bidirectional"))
    )
    (net (code "204") (name "Net-(X6A-S)") (class "Default")
      (node (ref "X6") (pin "1") (pinfunction "S_1") (pintype "passive"))
      (node (ref "X9") (pin "2") (pinfunction "S_2") (pintype "passive"))
    )
    (net (code "205") (name "Net-(X6D-S)") (class "Default")
      (node (ref "X6") (pin "4") (pinfunction "S_4") (pintype "passive"))
      (node (ref "X9") (pin "3") (pinfunction "S_3") (pintype "passive"))
    )
    (net (code "206") (name "Net-(Z_STOPB-S)") (class "Default")
      (node (ref "SJ1") (pin "2") (pinfunction "2_2") (pintype "passive"))
      (node (ref "SJ2") (pin "2") (pinfunction "2_2") (pintype "passive"))
      (node (ref "Z_STOP") (pin "2") (pinfunction "S_2") (pintype "passive"))
    )
    (net (code "207") (name "unconnected-(ESP1-ADC-Pad2)") (class "Default")
      (node (ref "ESP1") (pin "2") (pinfunction "ADC_2") (pintype "passive"))
    )
    (net (code "208") (name "unconnected-(ESP1-GPIO2-Pad11)") (class "Default")
      (node (ref "ESP1") (pin "11") (pinfunction "GPIO2_11") (pintype "bidirectional"))
    )
    (net (code "209") (name "unconnected-(ESP1-GPIO5-Pad13)") (class "Default")
      (node (ref "ESP1") (pin "13") (pinfunction "GPIO5_13") (pintype "bidirectional"))
    )
    (net (code "210") (name "unconnected-(ESP1-GPIO16-Pad4)") (class "Default")
      (node (ref "ESP1") (pin "4") (pinfunction "GPIO16_4") (pintype "bidirectional"))
    )
    (net (code "211") (name "unconnected-(EXP_1B-S-Pad10)") (class "Default")
      (node (ref "EXP_1") (pin "10") (pinfunction "S_10") (pintype "passive"))
    )
    (net (code "212") (name "unconnected-(EXP_1H-S-Pad7)") (class "Default")
      (node (ref "EXP_1") (pin "7") (pinfunction "S_7") (pintype "passive"))
    )
    (net (code "213") (name "unconnected-(EXP_1I-S-Pad8)") (class "Default")
      (node (ref "EXP_1") (pin "8") (pinfunction "S_8") (pintype "passive"))
    )
    (net (code "214") (name "unconnected-(EXP_2G-S-Pad6)") (class "Default")
      (node (ref "EXP_2") (pin "6") (pinfunction "S_6") (pintype "passive"))
    )
    (net (code "215") (name "unconnected-(EXP_2H-S-Pad7)") (class "Default")
      (node (ref "EXP_2") (pin "7") (pinfunction "S_7") (pintype "passive"))
    )
    (net (code "216") (name "unconnected-(EXP_2I-S-Pad8)") (class "Default")
      (node (ref "EXP_2") (pin "8") (pinfunction "S_8") (pintype "passive"))
    )
    (net (code "217") (name "unconnected-(IC2-PB2{slash}AD6-Pad7)") (class "Default")
      (node (ref "IC2") (pin "7") (pinfunction "PB2/AD6_7") (pintype "bidirectional"))
    )
    (net (code "218") (name "unconnected-(IC2-PB3{slash}AD7-Pad9)") (class "Default")
      (node (ref "IC2") (pin "9") (pinfunction "PB3/AD7_9") (pintype "bidirectional"))
    )
    (net (code "219") (name "unconnected-(IC2-PB13{slash}DAC0-Pad93)") (class "Default")
      (node (ref "IC2") (pin "93") (pinfunction "PB13/DAC0_93") (pintype "bidirectional"))
    )
    (net (code "220") (name "unconnected-(IC2-PC12{slash}AD12-Pad23)") (class "Default")
      (node (ref "IC2") (pin "23") (pinfunction "PC12/AD12_23") (pintype "bidirectional"))
    )
    (net (code "221") (name "unconnected-(IC2-PC18-Pad78)") (class "Default")
      (node (ref "IC2") (pin "78") (pinfunction "PC18_78") (pintype "bidirectional"))
    )
    (net (code "222") (name "unconnected-(IC2-PC24-Pad92)") (class "Default")
      (node (ref "IC2") (pin "92") (pinfunction "PC24_92") (pintype "bidirectional"))
    )
    (net (code "223") (name "unconnected-(IC2-PC25-Pad94)") (class "Default")
      (node (ref "IC2") (pin "94") (pinfunction "PC25_94") (pintype "bidirectional"))
    )
    (net (code "224") (name "unconnected-(IC2-PC27-Pad17)") (class "Default")
      (node (ref "IC2") (pin "17") (pinfunction "PC27_17") (pintype "bidirectional"))
    )
    (net (code "225") (name "unconnected-(IC2-PC31-Pad8)") (class "Default")
      (node (ref "IC2") (pin "8") (pinfunction "PC31_8") (pintype "bidirectional"))
    )
    (net (code "226") (name "unconnected-(IC2-TDO{slash}TRACESWO{slash}PB5-Pad76)") (class "Default")
      (node (ref "IC2") (pin "76") (pinfunction "TDO/TRACESWO/PB5_76") (pintype "bidirectional"))
    )
    (net (code "227") (name "unconnected-(IC2-TMS{slash}SWDIO{slash}PB6-Pad79)") (class "Default")
      (node (ref "IC2") (pin "79") (pinfunction "TMS/SWDIO/PB6_79") (pintype "bidirectional"))
    )
    (net (code "228") (name "unconnected-(IC4D-O-Pad11)") (class "Default")
      (node (ref "IC4") (pin "11") (pinfunction "O_11") (pintype "tri_state"))
    )
    (net (code "229") (name "unconnected-(IC5C-O-Pad8)") (class "Default")
      (node (ref "IC5") (pin "8") (pinfunction "O_8") (pintype "output"))
    )
    (net (code "230") (name "unconnected-(IC6-ENCA_DCIN_CFG5-Pad19)") (class "Default")
      (node (ref "IC6") (pin "19") (pinfunction "ENCA_DCIN_CFG5_19") (pintype "bidirectional"))
    )
    (net (code "231") (name "unconnected-(IC6-ENCN_DCO-Pad17)") (class "Default")
      (node (ref "IC6") (pin "17") (pinfunction "ENCN_DCO_17") (pintype "bidirectional"))
    )
    (net (code "232") (name "unconnected-(IC6-NC-Pad9)") (class "Default")
      (node (ref "IC6") (pin "9") (pinfunction "NC_9") (pintype "bidirectional"))
    )
    (net (code "233") (name "unconnected-(IC6-SPI_MODE-Pad10)") (class "Default")
      (node (ref "IC6") (pin "10") (pinfunction "SPI_MODE_10") (pintype "bidirectional"))
    )
    (net (code "234") (name "unconnected-(IC6-SWN_DIAG0-Pad20)") (class "Default")
      (node (ref "IC6") (pin "20") (pinfunction "SWN_DIAG0_20") (pintype "bidirectional"))
    )
    (net (code "235") (name "unconnected-(IC7-ENCA_DCIN_CFG5-Pad19)") (class "Default")
      (node (ref "IC7") (pin "19") (pinfunction "ENCA_DCIN_CFG5_19") (pintype "bidirectional"))
    )
    (net (code "236") (name "unconnected-(IC7-ENCN_DCO-Pad17)") (class "Default")
      (node (ref "IC7") (pin "17") (pinfunction "ENCN_DCO_17") (pintype "bidirectional"))
    )
    (net (code "237") (name "unconnected-(IC7-NC-Pad9)") (class "Default")
      (node (ref "IC7") (pin "9") (pinfunction "NC_9") (pintype "bidirectional"))
    )
    (net (code "238") (name "unconnected-(IC7-SPI_MODE-Pad10)") (class "Default")
      (node (ref "IC7") (pin "10") (pinfunction "SPI_MODE_10") (pintype "bidirectional"))
    )
    (net (code "239") (name "unconnected-(IC7-SWN_DIAG0-Pad20)") (class "Default")
      (node (ref "IC7") (pin "20") (pinfunction "SWN_DIAG0_20") (pintype "bidirectional"))
    )
    (net (code "240") (name "unconnected-(IC8-ENCA_DCIN_CFG5-Pad19)") (class "Default")
      (node (ref "IC8") (pin "19") (pinfunction "ENCA_DCIN_CFG5_19") (pintype "bidirectional"))
    )
    (net (code "241") (name "unconnected-(IC8-ENCN_DCO-Pad17)") (class "Default")
      (node (ref "IC8") (pin "17") (pinfunction "ENCN_DCO_17") (pintype "bidirectional"))
    )
    (net (code "242") (name "unconnected-(IC8-NC-Pad9)") (class "Default")
      (node (ref "IC8") (pin "9") (pinfunction "NC_9") (pintype "bidirectional"))
    )
    (net (code "243") (name "unconnected-(IC8-SPI_MODE-Pad10)") (class "Default")
      (node (ref "IC8") (pin "10") (pinfunction "SPI_MODE_10") (pintype "bidirectional"))
    )
    (net (code "244") (name "unconnected-(IC8-SWN_DIAG0-Pad20)") (class "Default")
      (node (ref "IC8") (pin "20") (pinfunction "SWN_DIAG0_20") (pintype "bidirectional"))
    )
    (net (code "245") (name "unconnected-(IC9-ENCA_DCIN_CFG5-Pad19)") (class "Default")
      (node (ref "IC9") (pin "19") (pinfunction "ENCA_DCIN_CFG5_19") (pintype "bidirectional"))
    )
    (net (code "246") (name "unconnected-(IC9-ENCN_DCO-Pad17)") (class "Default")
      (node (ref "IC9") (pin "17") (pinfunction "ENCN_DCO_17") (pintype "bidirectional"))
    )
    (net (code "247") (name "unconnected-(IC9-NC-Pad9)") (class "Default")
      (node (ref "IC9") (pin "9") (pinfunction "NC_9") (pintype "bidirectional"))
    )
    (net (code "248") (name "unconnected-(IC9-SPI_MODE-Pad10)") (class "Default")
      (node (ref "IC9") (pin "10") (pinfunction "SPI_MODE_10") (pintype "bidirectional"))
    )
    (net (code "249") (name "unconnected-(IC9-SWN_DIAG0-Pad20)") (class "Default")
      (node (ref "IC9") (pin "20") (pinfunction "SWN_DIAG0_20") (pintype "bidirectional"))
    )
    (net (code "250") (name "unconnected-(IC10-ENCA_DCIN_CFG5-Pad19)") (class "Default")
      (node (ref "IC10") (pin "19") (pinfunction "ENCA_DCIN_CFG5_19") (pintype "bidirectional"))
    )
    (net (code "251") (name "unconnected-(IC10-ENCN_DCO-Pad17)") (class "Default")
      (node (ref "IC10") (pin "17") (pinfunction "ENCN_DCO_17") (pintype "bidirectional"))
    )
    (net (code "252") (name "unconnected-(IC10-NC-Pad9)") (class "Default")
      (node (ref "IC10") (pin "9") (pinfunction "NC_9") (pintype "bidirectional"))
    )
    (net (code "253") (name "unconnected-(IC10-SPI_MODE-Pad10)") (class "Default")
      (node (ref "IC10") (pin "10") (pinfunction "SPI_MODE_10") (pintype "bidirectional"))
    )
    (net (code "254") (name "unconnected-(IC10-SWN_DIAG0-Pad20)") (class "Default")
      (node (ref "IC10") (pin "20") (pinfunction "SWN_DIAG0_20") (pintype "bidirectional"))
    )
    (net (code "255") (name "unconnected-(RESET-P1-PadA')") (class "Default")
      (node (ref "RESET") (pin "A'") (pinfunction "P1_A'") (pintype "passive"))
    )
  )
)
